# DDR4_SDRAM.net
KiCad netlist of a schematic drawn in Altium Designer
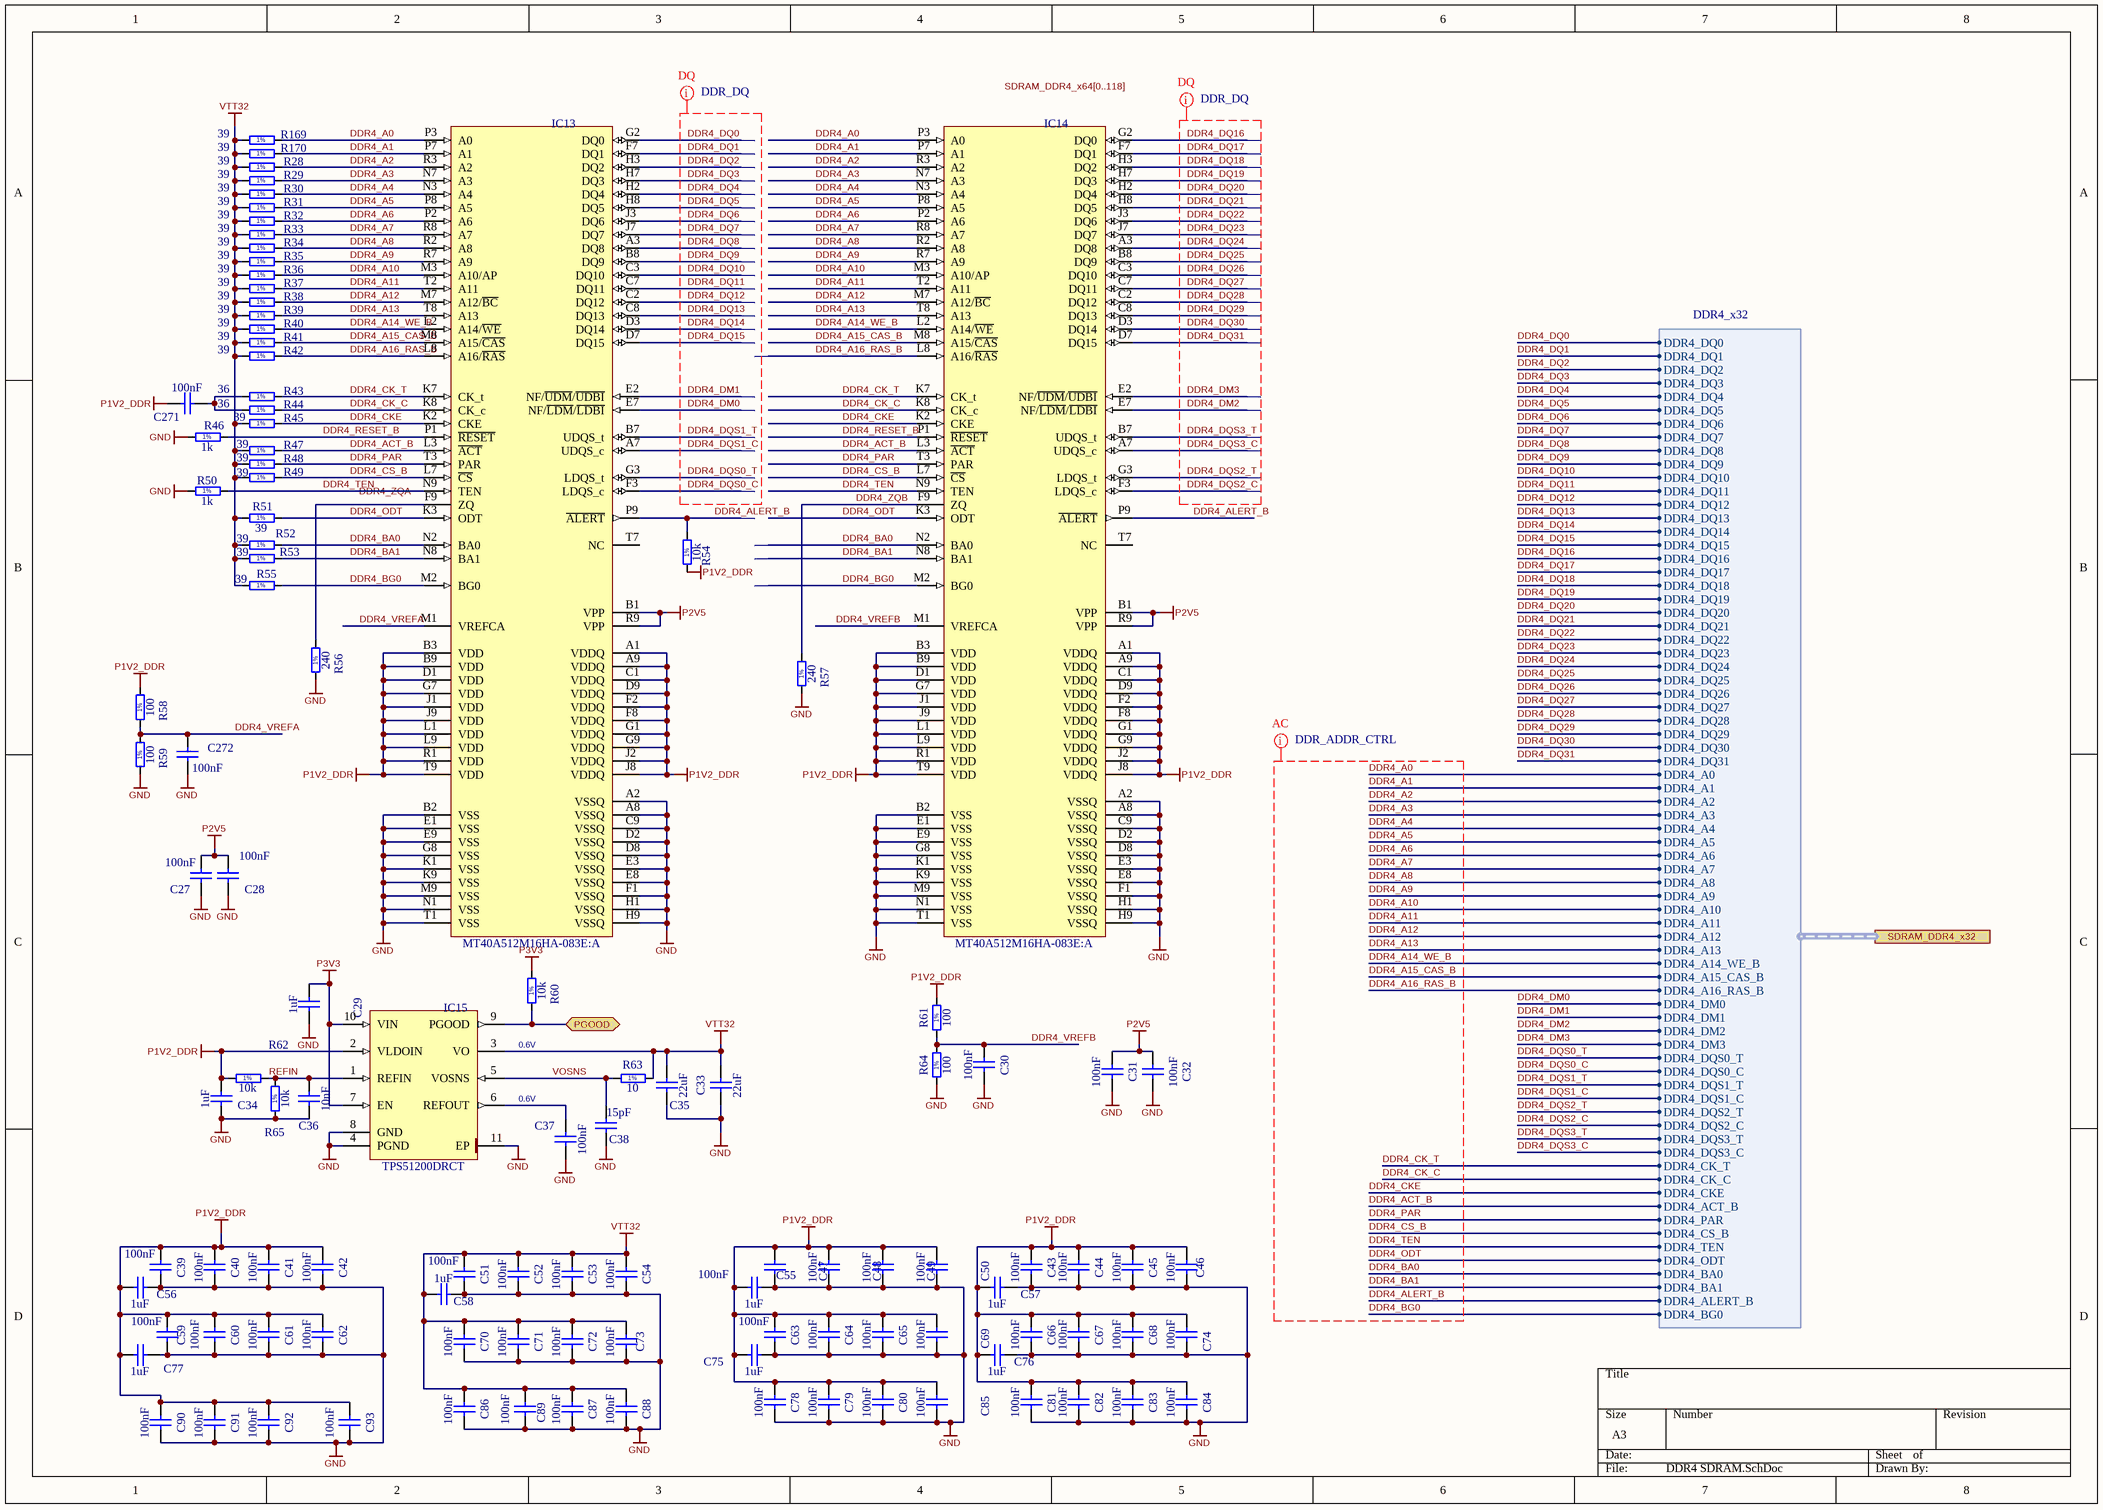
[diagram p0: DDR4 SDRAM.SchDoc]

(export (version "E")
  (design (tool "Eeschema 10.0.6"))
  (components
    (comp (ref "C27")
      (value "100nF")
      (footprint "CAPC0603X33N")
      (description "Non-polarised capacitor")
      (fields
        (field (name "MANUFACTURER PART NUMBER") "CC0201_100NF_6.3V_10%_X5R")
        (field (name "MANUFACTURER") "GENERIC")
        (field (name "AUTHOR") "CERN DEM JLC")
      )
      (libsource (lib "Capacitors") (part "Capacitor - non polarized"))
    )
    (comp (ref "C28")
      (value "100nF")
      (footprint "CAPC0603X33N")
      (description "Non-polarised capacitor")
      (fields
        (field (name "MANUFACTURER PART NUMBER") "CC0201_100NF_6.3V_10%_X5R")
        (field (name "MANUFACTURER") "GENERIC")
        (field (name "AUTHOR") "CERN DEM JLC")
      )
      (libsource (lib "Capacitors") (part "Capacitor - non polarized"))
    )
    (comp (ref "C29")
      (value "1uF")
      (footprint "CAPC1005X55N")
      (description "Non-polarised capacitor")
      (fields
        (field (name "MANUFACTURER PART NUMBER") "CC0402_1UF_16V_10%_X5R")
        (field (name "MANUFACTURER") "GENERIC")
        (field (name "AUTHOR") "CERN DEM JLC")
      )
      (libsource (lib "Capacitors") (part "Capacitor - non polarized"))
    )
    (comp (ref "C30")
      (value "100nF")
      (footprint "CAPC0603X33N")
      (description "Non-polarised capacitor")
      (fields
        (field (name "MANUFACTURER PART NUMBER") "CC0201_100NF_6.3V_10%_X5R")
        (field (name "MANUFACTURER") "GENERIC")
        (field (name "AUTHOR") "CERN DEM JLC")
      )
      (libsource (lib "Capacitors") (part "Capacitor - non polarized"))
    )
    (comp (ref "C31")
      (value "100nF")
      (footprint "CAPC0603X33N")
      (description "Non-polarised capacitor")
      (fields
        (field (name "MANUFACTURER PART NUMBER") "CC0201_100NF_6.3V_10%_X5R")
        (field (name "MANUFACTURER") "GENERIC")
        (field (name "AUTHOR") "CERN DEM JLC")
      )
      (libsource (lib "Capacitors") (part "Capacitor - non polarized"))
    )
    (comp (ref "C32")
      (value "100nF")
      (footprint "CAPC0603X33N")
      (description "Non-polarised capacitor")
      (fields
        (field (name "MANUFACTURER PART NUMBER") "CC0201_100NF_6.3V_10%_X5R")
        (field (name "MANUFACTURER") "GENERIC")
        (field (name "AUTHOR") "CERN DEM JLC")
      )
      (libsource (lib "Capacitors") (part "Capacitor - non polarized"))
    )
    (comp (ref "C33")
      (value "22uF")
      (footprint "CAPC2012X135N")
      (description "Non-polarised capacitor")
      (fields
        (field (name "MANUFACTURER PART NUMBER") "CC0805_22UF_10V_+80%-20%_Y5V")
        (field (name "MANUFACTURER") "GENERIC")
        (field (name "AUTHOR") "CERN DEM JLC")
      )
      (libsource (lib "Capacitors") (part "Capacitor - non polarized"))
    )
    (comp (ref "C34")
      (value "1uF")
      (footprint "CAPC1005X55N")
      (description "Non-polarised capacitor")
      (fields
        (field (name "MANUFACTURER PART NUMBER") "CC0402_1UF_16V_10%_X5R")
        (field (name "MANUFACTURER") "GENERIC")
        (field (name "AUTHOR") "CERN DEM JLC")
      )
      (libsource (lib "Capacitors") (part "Capacitor - non polarized"))
    )
    (comp (ref "C35")
      (value "22uF")
      (footprint "CAPC2012X135N")
      (description "Non-polarised capacitor")
      (fields
        (field (name "MANUFACTURER PART NUMBER") "CC0805_22UF_10V_+80%-20%_Y5V")
        (field (name "MANUFACTURER") "GENERIC")
        (field (name "AUTHOR") "CERN DEM JLC")
      )
      (libsource (lib "Capacitors") (part "Capacitor - non polarized"))
    )
    (comp (ref "C36")
      (value "10nF")
      (footprint "CAPC1005X55N")
      (description "Non-polarised capacitor")
      (fields
        (field (name "MANUFACTURER PART NUMBER") "CC0402_10NF_25V_10%_X7R")
        (field (name "MANUFACTURER") "GENERIC")
        (field (name "AUTHOR") "CERN DEM JLC")
      )
      (libsource (lib "Capacitors") (part "Capacitor - non polarized"))
    )
    (comp (ref "C37")
      (value "100nF")
      (footprint "CAPC0603X33N")
      (description "Non-polarised capacitor")
      (fields
        (field (name "MANUFACTURER PART NUMBER") "CC0201_100NF_6.3V_10%_X5R")
        (field (name "MANUFACTURER") "GENERIC")
        (field (name "AUTHOR") "CERN DEM JLC")
      )
      (libsource (lib "Capacitors") (part "Capacitor - non polarized"))
    )
    (comp (ref "C38")
      (value "15pF")
      (footprint "CAPC1005X55N")
      (description "Non-polarised capacitor")
      (fields
        (field (name "MANUFACTURER PART NUMBER") "CC0402_15PF_50V_5%_C0G")
        (field (name "MANUFACTURER") "GENERIC")
        (field (name "AUTHOR") "CERN DEM JLC")
      )
      (libsource (lib "Capacitors") (part "Capacitor - non polarized"))
    )
    (comp (ref "C39")
      (value "100nF")
      (footprint "CAPC0603X33N")
      (description "Non-polarised capacitor")
      (fields
        (field (name "MANUFACTURER PART NUMBER") "CC0201_100NF_6.3V_10%_X5R")
        (field (name "MANUFACTURER") "GENERIC")
        (field (name "AUTHOR") "CERN DEM JLC")
      )
      (libsource (lib "Capacitors") (part "Capacitor - non polarized"))
    )
    (comp (ref "C40")
      (value "100nF")
      (footprint "CAPC0603X33N")
      (description "Non-polarised capacitor")
      (fields
        (field (name "MANUFACTURER PART NUMBER") "CC0201_100NF_6.3V_10%_X5R")
        (field (name "MANUFACTURER") "GENERIC")
        (field (name "AUTHOR") "CERN DEM JLC")
      )
      (libsource (lib "Capacitors") (part "Capacitor - non polarized"))
    )
    (comp (ref "C41")
      (value "100nF")
      (footprint "CAPC0603X33N")
      (description "Non-polarised capacitor")
      (fields
        (field (name "MANUFACTURER PART NUMBER") "CC0201_100NF_6.3V_10%_X5R")
        (field (name "MANUFACTURER") "GENERIC")
        (field (name "AUTHOR") "CERN DEM JLC")
      )
      (libsource (lib "Capacitors") (part "Capacitor - non polarized"))
    )
    (comp (ref "C42")
      (value "100nF")
      (footprint "CAPC0603X33N")
      (description "Non-polarised capacitor")
      (fields
        (field (name "MANUFACTURER PART NUMBER") "CC0201_100NF_6.3V_10%_X5R")
        (field (name "MANUFACTURER") "GENERIC")
        (field (name "AUTHOR") "CERN DEM JLC")
      )
      (libsource (lib "Capacitors") (part "Capacitor - non polarized"))
    )
    (comp (ref "C43")
      (value "100nF")
      (footprint "CAPC0603X33N")
      (description "Non-polarised capacitor")
      (fields
        (field (name "MANUFACTURER PART NUMBER") "CC0201_100NF_6.3V_10%_X5R")
        (field (name "MANUFACTURER") "GENERIC")
        (field (name "AUTHOR") "CERN DEM JLC")
      )
      (libsource (lib "Capacitors") (part "Capacitor - non polarized"))
    )
    (comp (ref "C44")
      (value "100nF")
      (footprint "CAPC0603X33N")
      (description "Non-polarised capacitor")
      (fields
        (field (name "MANUFACTURER PART NUMBER") "CC0201_100NF_6.3V_10%_X5R")
        (field (name "MANUFACTURER") "GENERIC")
        (field (name "AUTHOR") "CERN DEM JLC")
      )
      (libsource (lib "Capacitors") (part "Capacitor - non polarized"))
    )
    (comp (ref "C45")
      (value "100nF")
      (footprint "CAPC0603X33N")
      (description "Non-polarised capacitor")
      (fields
        (field (name "MANUFACTURER PART NUMBER") "CC0201_100NF_6.3V_10%_X5R")
        (field (name "MANUFACTURER") "GENERIC")
        (field (name "AUTHOR") "CERN DEM JLC")
      )
      (libsource (lib "Capacitors") (part "Capacitor - non polarized"))
    )
    (comp (ref "C46")
      (value "100nF")
      (footprint "CAPC0603X33N")
      (description "Non-polarised capacitor")
      (fields
        (field (name "MANUFACTURER PART NUMBER") "CC0201_100NF_6.3V_10%_X5R")
        (field (name "MANUFACTURER") "GENERIC")
        (field (name "AUTHOR") "CERN DEM JLC")
      )
      (libsource (lib "Capacitors") (part "Capacitor - non polarized"))
    )
    (comp (ref "C47")
      (value "100nF")
      (footprint "CAPC0603X33N")
      (description "Non-polarised capacitor")
      (fields
        (field (name "MANUFACTURER PART NUMBER") "CC0201_100NF_6.3V_10%_X5R")
        (field (name "MANUFACTURER") "GENERIC")
        (field (name "AUTHOR") "CERN DEM JLC")
      )
      (libsource (lib "Capacitors") (part "Capacitor - non polarized"))
    )
    (comp (ref "C48")
      (value "100nF")
      (footprint "CAPC0603X33N")
      (description "Non-polarised capacitor")
      (fields
        (field (name "MANUFACTURER PART NUMBER") "CC0201_100NF_6.3V_10%_X5R")
        (field (name "MANUFACTURER") "GENERIC")
        (field (name "AUTHOR") "CERN DEM JLC")
      )
      (libsource (lib "Capacitors") (part "Capacitor - non polarized"))
    )
    (comp (ref "C49")
      (value "100nF")
      (footprint "CAPC0603X33N")
      (description "Non-polarised capacitor")
      (fields
        (field (name "MANUFACTURER PART NUMBER") "CC0201_100NF_6.3V_10%_X5R")
        (field (name "MANUFACTURER") "GENERIC")
        (field (name "AUTHOR") "CERN DEM JLC")
      )
      (libsource (lib "Capacitors") (part "Capacitor - non polarized"))
    )
    (comp (ref "C50")
      (value "100nF")
      (footprint "CAPC0603X33N")
      (description "Non-polarised capacitor")
      (fields
        (field (name "MANUFACTURER PART NUMBER") "CC0201_100NF_6.3V_10%_X5R")
        (field (name "MANUFACTURER") "GENERIC")
        (field (name "AUTHOR") "CERN DEM JLC")
      )
      (libsource (lib "Capacitors") (part "Capacitor - non polarized"))
    )
    (comp (ref "C51")
      (value "100nF")
      (footprint "CAPC0603X33N")
      (description "Non-polarised capacitor")
      (fields
        (field (name "MANUFACTURER PART NUMBER") "CC0201_100NF_6.3V_10%_X5R")
        (field (name "MANUFACTURER") "GENERIC")
        (field (name "AUTHOR") "CERN DEM JLC")
      )
      (libsource (lib "Capacitors") (part "Capacitor - non polarized"))
    )
    (comp (ref "C52")
      (value "100nF")
      (footprint "CAPC0603X33N")
      (description "Non-polarised capacitor")
      (fields
        (field (name "MANUFACTURER PART NUMBER") "CC0201_100NF_6.3V_10%_X5R")
        (field (name "MANUFACTURER") "GENERIC")
        (field (name "AUTHOR") "CERN DEM JLC")
      )
      (libsource (lib "Capacitors") (part "Capacitor - non polarized"))
    )
    (comp (ref "C53")
      (value "100nF")
      (footprint "CAPC0603X33N")
      (description "Non-polarised capacitor")
      (fields
        (field (name "MANUFACTURER PART NUMBER") "CC0201_100NF_6.3V_10%_X5R")
        (field (name "MANUFACTURER") "GENERIC")
        (field (name "AUTHOR") "CERN DEM JLC")
      )
      (libsource (lib "Capacitors") (part "Capacitor - non polarized"))
    )
    (comp (ref "C54")
      (value "100nF")
      (footprint "CAPC0603X33N")
      (description "Non-polarised capacitor")
      (fields
        (field (name "MANUFACTURER PART NUMBER") "CC0201_100NF_6.3V_10%_X5R")
        (field (name "MANUFACTURER") "GENERIC")
        (field (name "AUTHOR") "CERN DEM JLC")
      )
      (libsource (lib "Capacitors") (part "Capacitor - non polarized"))
    )
    (comp (ref "C55")
      (value "1uF")
      (footprint "CAPC1005X55N")
      (description "Non-polarised capacitor")
      (fields
        (field (name "MANUFACTURER PART NUMBER") "CC0402_1UF_16V_10%_X5R")
        (field (name "MANUFACTURER") "GENERIC")
        (field (name "AUTHOR") "CERN DEM JLC")
      )
      (libsource (lib "Capacitors") (part "Capacitor - non polarized"))
    )
    (comp (ref "C56")
      (value "1uF")
      (footprint "CAPC1005X55N")
      (description "Non-polarised capacitor")
      (fields
        (field (name "MANUFACTURER PART NUMBER") "CC0402_1UF_16V_10%_X5R")
        (field (name "MANUFACTURER") "GENERIC")
        (field (name "AUTHOR") "CERN DEM JLC")
      )
      (libsource (lib "Capacitors") (part "Capacitor - non polarized"))
    )
    (comp (ref "C57")
      (value "1uF")
      (footprint "CAPC1005X55N")
      (description "Non-polarised capacitor")
      (fields
        (field (name "MANUFACTURER PART NUMBER") "CC0402_1UF_16V_10%_X5R")
        (field (name "MANUFACTURER") "GENERIC")
        (field (name "AUTHOR") "CERN DEM JLC")
      )
      (libsource (lib "Capacitors") (part "Capacitor - non polarized"))
    )
    (comp (ref "C58")
      (value "1uF")
      (footprint "CAPC1005X55N")
      (description "Non-polarised capacitor")
      (fields
        (field (name "MANUFACTURER PART NUMBER") "CC0402_1UF_16V_10%_X5R")
        (field (name "MANUFACTURER") "GENERIC")
        (field (name "AUTHOR") "CERN DEM JLC")
      )
      (libsource (lib "Capacitors") (part "Capacitor - non polarized"))
    )
    (comp (ref "C59")
      (value "100nF")
      (footprint "CAPC0603X33N")
      (description "Non-polarised capacitor")
      (fields
        (field (name "MANUFACTURER PART NUMBER") "CC0201_100NF_6.3V_10%_X5R")
        (field (name "MANUFACTURER") "GENERIC")
        (field (name "AUTHOR") "CERN DEM JLC")
      )
      (libsource (lib "Capacitors") (part "Capacitor - non polarized"))
    )
    (comp (ref "C60")
      (value "100nF")
      (footprint "CAPC0603X33N")
      (description "Non-polarised capacitor")
      (fields
        (field (name "MANUFACTURER PART NUMBER") "CC0201_100NF_6.3V_10%_X5R")
        (field (name "MANUFACTURER") "GENERIC")
        (field (name "AUTHOR") "CERN DEM JLC")
      )
      (libsource (lib "Capacitors") (part "Capacitor - non polarized"))
    )
    (comp (ref "C61")
      (value "100nF")
      (footprint "CAPC0603X33N")
      (description "Non-polarised capacitor")
      (fields
        (field (name "MANUFACTURER PART NUMBER") "CC0201_100NF_6.3V_10%_X5R")
        (field (name "MANUFACTURER") "GENERIC")
        (field (name "AUTHOR") "CERN DEM JLC")
      )
      (libsource (lib "Capacitors") (part "Capacitor - non polarized"))
    )
    (comp (ref "C62")
      (value "100nF")
      (footprint "CAPC0603X33N")
      (description "Non-polarised capacitor")
      (fields
        (field (name "MANUFACTURER PART NUMBER") "CC0201_100NF_6.3V_10%_X5R")
        (field (name "MANUFACTURER") "GENERIC")
        (field (name "AUTHOR") "CERN DEM JLC")
      )
      (libsource (lib "Capacitors") (part "Capacitor - non polarized"))
    )
    (comp (ref "C63")
      (value "100nF")
      (footprint "CAPC0603X33N")
      (description "Non-polarised capacitor")
      (fields
        (field (name "MANUFACTURER PART NUMBER") "CC0201_100NF_6.3V_10%_X5R")
        (field (name "MANUFACTURER") "GENERIC")
        (field (name "AUTHOR") "CERN DEM JLC")
      )
      (libsource (lib "Capacitors") (part "Capacitor - non polarized"))
    )
    (comp (ref "C64")
      (value "100nF")
      (footprint "CAPC0603X33N")
      (description "Non-polarised capacitor")
      (fields
        (field (name "MANUFACTURER PART NUMBER") "CC0201_100NF_6.3V_10%_X5R")
        (field (name "MANUFACTURER") "GENERIC")
        (field (name "AUTHOR") "CERN DEM JLC")
      )
      (libsource (lib "Capacitors") (part "Capacitor - non polarized"))
    )
    (comp (ref "C65")
      (value "100nF")
      (footprint "CAPC0603X33N")
      (description "Non-polarised capacitor")
      (fields
        (field (name "MANUFACTURER PART NUMBER") "CC0201_100NF_6.3V_10%_X5R")
        (field (name "MANUFACTURER") "GENERIC")
        (field (name "AUTHOR") "CERN DEM JLC")
      )
      (libsource (lib "Capacitors") (part "Capacitor - non polarized"))
    )
    (comp (ref "C66")
      (value "100nF")
      (footprint "CAPC0603X33N")
      (description "Non-polarised capacitor")
      (fields
        (field (name "MANUFACTURER PART NUMBER") "CC0201_100NF_6.3V_10%_X5R")
        (field (name "MANUFACTURER") "GENERIC")
        (field (name "AUTHOR") "CERN DEM JLC")
      )
      (libsource (lib "Capacitors") (part "Capacitor - non polarized"))
    )
    (comp (ref "C67")
      (value "100nF")
      (footprint "CAPC0603X33N")
      (description "Non-polarised capacitor")
      (fields
        (field (name "MANUFACTURER PART NUMBER") "CC0201_100NF_6.3V_10%_X5R")
        (field (name "MANUFACTURER") "GENERIC")
        (field (name "AUTHOR") "CERN DEM JLC")
      )
      (libsource (lib "Capacitors") (part "Capacitor - non polarized"))
    )
    (comp (ref "C68")
      (value "100nF")
      (footprint "CAPC0603X33N")
      (description "Non-polarised capacitor")
      (fields
        (field (name "MANUFACTURER PART NUMBER") "CC0201_100NF_6.3V_10%_X5R")
        (field (name "MANUFACTURER") "GENERIC")
        (field (name "AUTHOR") "CERN DEM JLC")
      )
      (libsource (lib "Capacitors") (part "Capacitor - non polarized"))
    )
    (comp (ref "C69")
      (value "100nF")
      (footprint "CAPC0603X33N")
      (description "Non-polarised capacitor")
      (fields
        (field (name "MANUFACTURER PART NUMBER") "CC0201_100NF_6.3V_10%_X5R")
        (field (name "MANUFACTURER") "GENERIC")
        (field (name "AUTHOR") "CERN DEM JLC")
      )
      (libsource (lib "Capacitors") (part "Capacitor - non polarized"))
    )
    (comp (ref "C70")
      (value "100nF")
      (footprint "CAPC0603X33N")
      (description "Non-polarised capacitor")
      (fields
        (field (name "MANUFACTURER PART NUMBER") "CC0201_100NF_6.3V_10%_X5R")
        (field (name "MANUFACTURER") "GENERIC")
        (field (name "AUTHOR") "CERN DEM JLC")
      )
      (libsource (lib "Capacitors") (part "Capacitor - non polarized"))
    )
    (comp (ref "C71")
      (value "100nF")
      (footprint "CAPC0603X33N")
      (description "Non-polarised capacitor")
      (fields
        (field (name "MANUFACTURER PART NUMBER") "CC0201_100NF_6.3V_10%_X5R")
        (field (name "MANUFACTURER") "GENERIC")
        (field (name "AUTHOR") "CERN DEM JLC")
      )
      (libsource (lib "Capacitors") (part "Capacitor - non polarized"))
    )
    (comp (ref "C72")
      (value "100nF")
      (footprint "CAPC0603X33N")
      (description "Non-polarised capacitor")
      (fields
        (field (name "MANUFACTURER PART NUMBER") "CC0201_100NF_6.3V_10%_X5R")
        (field (name "MANUFACTURER") "GENERIC")
        (field (name "AUTHOR") "CERN DEM JLC")
      )
      (libsource (lib "Capacitors") (part "Capacitor - non polarized"))
    )
    (comp (ref "C73")
      (value "100nF")
      (footprint "CAPC0603X33N")
      (description "Non-polarised capacitor")
      (fields
        (field (name "MANUFACTURER PART NUMBER") "CC0201_100NF_6.3V_10%_X5R")
        (field (name "MANUFACTURER") "GENERIC")
        (field (name "AUTHOR") "CERN DEM JLC")
      )
      (libsource (lib "Capacitors") (part "Capacitor - non polarized"))
    )
    (comp (ref "C74")
      (value "100nF")
      (footprint "CAPC0603X33N")
      (description "Non-polarised capacitor")
      (fields
        (field (name "MANUFACTURER PART NUMBER") "CC0201_100NF_6.3V_10%_X5R")
        (field (name "MANUFACTURER") "GENERIC")
        (field (name "AUTHOR") "CERN DEM JLC")
      )
      (libsource (lib "Capacitors") (part "Capacitor - non polarized"))
    )
    (comp (ref "C75")
      (value "1uF")
      (footprint "CAPC1005X55N")
      (description "Non-polarised capacitor")
      (fields
        (field (name "MANUFACTURER PART NUMBER") "CC0402_1UF_16V_10%_X5R")
        (field (name "MANUFACTURER") "GENERIC")
        (field (name "AUTHOR") "CERN DEM JLC")
      )
      (libsource (lib "Capacitors") (part "Capacitor - non polarized"))
    )
    (comp (ref "C76")
      (value "1uF")
      (footprint "CAPC1005X55N")
      (description "Non-polarised capacitor")
      (fields
        (field (name "MANUFACTURER PART NUMBER") "CC0402_1UF_16V_10%_X5R")
        (field (name "MANUFACTURER") "GENERIC")
        (field (name "AUTHOR") "CERN DEM JLC")
      )
      (libsource (lib "Capacitors") (part "Capacitor - non polarized"))
    )
    (comp (ref "C77")
      (value "1uF")
      (footprint "CAPC1005X55N")
      (description "Non-polarised capacitor")
      (fields
        (field (name "MANUFACTURER PART NUMBER") "CC0402_1UF_16V_10%_X5R")
        (field (name "MANUFACTURER") "GENERIC")
        (field (name "AUTHOR") "CERN DEM JLC")
      )
      (libsource (lib "Capacitors") (part "Capacitor - non polarized"))
    )
    (comp (ref "C78")
      (value "100nF")
      (footprint "CAPC0603X33N")
      (description "Non-polarised capacitor")
      (fields
        (field (name "MANUFACTURER PART NUMBER") "CC0201_100NF_6.3V_10%_X5R")
        (field (name "MANUFACTURER") "GENERIC")
        (field (name "AUTHOR") "CERN DEM JLC")
      )
      (libsource (lib "Capacitors") (part "Capacitor - non polarized"))
    )
    (comp (ref "C79")
      (value "100nF")
      (footprint "CAPC0603X33N")
      (description "Non-polarised capacitor")
      (fields
        (field (name "MANUFACTURER PART NUMBER") "CC0201_100NF_6.3V_10%_X5R")
        (field (name "MANUFACTURER") "GENERIC")
        (field (name "AUTHOR") "CERN DEM JLC")
      )
      (libsource (lib "Capacitors") (part "Capacitor - non polarized"))
    )
    (comp (ref "C80")
      (value "100nF")
      (footprint "CAPC0603X33N")
      (description "Non-polarised capacitor")
      (fields
        (field (name "MANUFACTURER PART NUMBER") "CC0201_100NF_6.3V_10%_X5R")
        (field (name "MANUFACTURER") "GENERIC")
        (field (name "AUTHOR") "CERN DEM JLC")
      )
      (libsource (lib "Capacitors") (part "Capacitor - non polarized"))
    )
    (comp (ref "C81")
      (value "100nF")
      (footprint "CAPC0603X33N")
      (description "Non-polarised capacitor")
      (fields
        (field (name "MANUFACTURER PART NUMBER") "CC0201_100NF_6.3V_10%_X5R")
        (field (name "MANUFACTURER") "GENERIC")
        (field (name "AUTHOR") "CERN DEM JLC")
      )
      (libsource (lib "Capacitors") (part "Capacitor - non polarized"))
    )
    (comp (ref "C82")
      (value "100nF")
      (footprint "CAPC0603X33N")
      (description "Non-polarised capacitor")
      (fields
        (field (name "MANUFACTURER PART NUMBER") "CC0201_100NF_6.3V_10%_X5R")
        (field (name "MANUFACTURER") "GENERIC")
        (field (name "AUTHOR") "CERN DEM JLC")
      )
      (libsource (lib "Capacitors") (part "Capacitor - non polarized"))
    )
    (comp (ref "C83")
      (value "100nF")
      (footprint "CAPC0603X33N")
      (description "Non-polarised capacitor")
      (fields
        (field (name "MANUFACTURER PART NUMBER") "CC0201_100NF_6.3V_10%_X5R")
        (field (name "MANUFACTURER") "GENERIC")
        (field (name "AUTHOR") "CERN DEM JLC")
      )
      (libsource (lib "Capacitors") (part "Capacitor - non polarized"))
    )
    (comp (ref "C84")
      (value "100nF")
      (footprint "CAPC0603X33N")
      (description "Non-polarised capacitor")
      (fields
        (field (name "MANUFACTURER PART NUMBER") "CC0201_100NF_6.3V_10%_X5R")
        (field (name "MANUFACTURER") "GENERIC")
        (field (name "AUTHOR") "CERN DEM JLC")
      )
      (libsource (lib "Capacitors") (part "Capacitor - non polarized"))
    )
    (comp (ref "C85")
      (value "100nF")
      (footprint "CAPC0603X33N")
      (description "Non-polarised capacitor")
      (fields
        (field (name "MANUFACTURER PART NUMBER") "CC0201_100NF_6.3V_10%_X5R")
        (field (name "MANUFACTURER") "GENERIC")
        (field (name "AUTHOR") "CERN DEM JLC")
      )
      (libsource (lib "Capacitors") (part "Capacitor - non polarized"))
    )
    (comp (ref "C86")
      (value "100nF")
      (footprint "CAPC0603X33N")
      (description "Non-polarised capacitor")
      (fields
        (field (name "MANUFACTURER PART NUMBER") "CC0201_100NF_6.3V_10%_X5R")
        (field (name "MANUFACTURER") "GENERIC")
        (field (name "AUTHOR") "CERN DEM JLC")
      )
      (libsource (lib "Capacitors") (part "Capacitor - non polarized"))
    )
    (comp (ref "C87")
      (value "100nF")
      (footprint "CAPC0603X33N")
      (description "Non-polarised capacitor")
      (fields
        (field (name "MANUFACTURER PART NUMBER") "CC0201_100NF_6.3V_10%_X5R")
        (field (name "MANUFACTURER") "GENERIC")
        (field (name "AUTHOR") "CERN DEM JLC")
      )
      (libsource (lib "Capacitors") (part "Capacitor - non polarized"))
    )
    (comp (ref "C88")
      (value "100nF")
      (footprint "CAPC0603X33N")
      (description "Non-polarised capacitor")
      (fields
        (field (name "MANUFACTURER PART NUMBER") "CC0201_100NF_6.3V_10%_X5R")
        (field (name "MANUFACTURER") "GENERIC")
        (field (name "AUTHOR") "CERN DEM JLC")
      )
      (libsource (lib "Capacitors") (part "Capacitor - non polarized"))
    )
    (comp (ref "C89")
      (value "100nF")
      (footprint "CAPC0603X33N")
      (description "Non-polarised capacitor")
      (fields
        (field (name "MANUFACTURER PART NUMBER") "CC0201_100NF_6.3V_10%_X5R")
        (field (name "MANUFACTURER") "GENERIC")
        (field (name "AUTHOR") "CERN DEM JLC")
      )
      (libsource (lib "Capacitors") (part "Capacitor - non polarized"))
    )
    (comp (ref "C90")
      (value "100nF")
      (footprint "CAPC0603X33N")
      (description "Non-polarised capacitor")
      (fields
        (field (name "MANUFACTURER PART NUMBER") "CC0201_100NF_6.3V_10%_X5R")
        (field (name "MANUFACTURER") "GENERIC")
        (field (name "AUTHOR") "CERN DEM JLC")
      )
      (libsource (lib "Capacitors") (part "Capacitor - non polarized"))
    )
    (comp (ref "C91")
      (value "100nF")
      (footprint "CAPC0603X33N")
      (description "Non-polarised capacitor")
      (fields
        (field (name "MANUFACTURER PART NUMBER") "CC0201_100NF_6.3V_10%_X5R")
        (field (name "MANUFACTURER") "GENERIC")
        (field (name "AUTHOR") "CERN DEM JLC")
      )
      (libsource (lib "Capacitors") (part "Capacitor - non polarized"))
    )
    (comp (ref "C92")
      (value "100nF")
      (footprint "CAPC0603X33N")
      (description "Non-polarised capacitor")
      (fields
        (field (name "MANUFACTURER PART NUMBER") "CC0201_100NF_6.3V_10%_X5R")
        (field (name "MANUFACTURER") "GENERIC")
        (field (name "AUTHOR") "CERN DEM JLC")
      )
      (libsource (lib "Capacitors") (part "Capacitor - non polarized"))
    )
    (comp (ref "C93")
      (value "100nF")
      (footprint "CAPC0603X33N")
      (description "Non-polarised capacitor")
      (fields
        (field (name "MANUFACTURER PART NUMBER") "CC0201_100NF_6.3V_10%_X5R")
        (field (name "MANUFACTURER") "GENERIC")
        (field (name "AUTHOR") "CERN DEM JLC")
      )
      (libsource (lib "Capacitors") (part "Capacitor - non polarized"))
    )
    (comp (ref "C271")
      (value "100nF")
      (footprint "CAPC0603X33N")
      (description "Non-polarised capacitor")
      (fields
        (field (name "MANUFACTURER PART NUMBER") "CC0201_100NF_6.3V_10%_X5R")
        (field (name "MANUFACTURER") "GENERIC")
        (field (name "AUTHOR") "CERN DEM JLC")
      )
      (libsource (lib "Capacitors") (part "Capacitor - non polarized"))
    )
    (comp (ref "C272")
      (value "100nF")
      (footprint "CAPC0603X33N")
      (description "Non-polarised capacitor")
      (fields
        (field (name "MANUFACTURER PART NUMBER") "CC0201_100NF_6.3V_10%_X5R")
        (field (name "MANUFACTURER") "GENERIC")
        (field (name "AUTHOR") "CERN DEM JLC")
      )
      (libsource (lib "Capacitors") (part "Capacitor - non polarized"))
    )
    (comp (ref "IC13")
      (value "MT40A512M16HA-083E:A")
      (footprint "BGA96C80P9X16_900X1400X120")
      (description "+1.2V, 8Gb (512 Meg x 16 x 8 Banks) DDR4 SDRAM")
      (fields (field (name "MANUFACTURER") "MICRON TECHNOLOGY") (field (name "AUTHOR") "CERN DEM MR"))
      (libsource (lib "ICs And Semiconductors") (part "MT40A512M16HA"))
    )
    (comp (ref "IC14")
      (value "MT40A512M16HA-083E:A")
      (footprint "BGA96C80P9X16_900X1400X120")
      (description "+1.2V, 8Gb (512 Meg x 16 x 8 Banks) DDR4 SDRAM")
      (fields (field (name "MANUFACTURER") "MICRON TECHNOLOGY") (field (name "AUTHOR") "CERN DEM MR"))
      (libsource (lib "ICs And Semiconductors") (part "MT40A512M16HA"))
    )
    (comp (ref "IC15")
      (value "TPS51200DRCT")
      (footprint "TEXAS_DRC (S-PVSON-N10)")
      (description "Sink/Source DDR Termination Regulator")
      (fields (field (name "MANUFACTURER") "TEXAS INSTRUMENTS") (field (name "AUTHOR") "CERN DEM JLC"))
      (libsource (lib "ICs And Semiconductors") (part "TPS51200DRC"))
    )
    (comp (ref "R28")
      (value "39")
      (footprint "RESC1005X40N")
      (description "Resistor - 1%")
      (fields
        (field (name "MANUFACTURER PART NUMBER") "R0402_39R_1%_0.0625W_100PPM")
        (field (name "MANUFACTURER") "GENERIC")
        (field (name "AUTHOR") "CERN DEM JLC")
      )
      (libsource (lib "Resistors") (part "Resistor - 1%"))
    )
    (comp (ref "R29")
      (value "39")
      (footprint "RESC1005X40N")
      (description "Resistor - 1%")
      (fields
        (field (name "MANUFACTURER PART NUMBER") "R0402_39R_1%_0.0625W_100PPM")
        (field (name "MANUFACTURER") "GENERIC")
        (field (name "AUTHOR") "CERN DEM JLC")
      )
      (libsource (lib "Resistors") (part "Resistor - 1%"))
    )
    (comp (ref "R30")
      (value "39")
      (footprint "RESC1005X40N")
      (description "Resistor - 1%")
      (fields
        (field (name "MANUFACTURER PART NUMBER") "R0402_39R_1%_0.0625W_100PPM")
        (field (name "MANUFACTURER") "GENERIC")
        (field (name "AUTHOR") "CERN DEM JLC")
      )
      (libsource (lib "Resistors") (part "Resistor - 1%"))
    )
    (comp (ref "R31")
      (value "39")
      (footprint "RESC1005X40N")
      (description "Resistor - 1%")
      (fields
        (field (name "MANUFACTURER PART NUMBER") "R0402_39R_1%_0.0625W_100PPM")
        (field (name "MANUFACTURER") "GENERIC")
        (field (name "AUTHOR") "CERN DEM JLC")
      )
      (libsource (lib "Resistors") (part "Resistor - 1%"))
    )
    (comp (ref "R32")
      (value "39")
      (footprint "RESC1005X40N")
      (description "Resistor - 1%")
      (fields
        (field (name "MANUFACTURER PART NUMBER") "R0402_39R_1%_0.0625W_100PPM")
        (field (name "MANUFACTURER") "GENERIC")
        (field (name "AUTHOR") "CERN DEM JLC")
      )
      (libsource (lib "Resistors") (part "Resistor - 1%"))
    )
    (comp (ref "R33")
      (value "39")
      (footprint "RESC1005X40N")
      (description "Resistor - 1%")
      (fields
        (field (name "MANUFACTURER PART NUMBER") "R0402_39R_1%_0.0625W_100PPM")
        (field (name "MANUFACTURER") "GENERIC")
        (field (name "AUTHOR") "CERN DEM JLC")
      )
      (libsource (lib "Resistors") (part "Resistor - 1%"))
    )
    (comp (ref "R34")
      (value "39")
      (footprint "RESC1005X40N")
      (description "Resistor - 1%")
      (fields
        (field (name "MANUFACTURER PART NUMBER") "R0402_39R_1%_0.0625W_100PPM")
        (field (name "MANUFACTURER") "GENERIC")
        (field (name "AUTHOR") "CERN DEM JLC")
      )
      (libsource (lib "Resistors") (part "Resistor - 1%"))
    )
    (comp (ref "R35")
      (value "39")
      (footprint "RESC1005X40N")
      (description "Resistor - 1%")
      (fields
        (field (name "MANUFACTURER PART NUMBER") "R0402_39R_1%_0.0625W_100PPM")
        (field (name "MANUFACTURER") "GENERIC")
        (field (name "AUTHOR") "CERN DEM JLC")
      )
      (libsource (lib "Resistors") (part "Resistor - 1%"))
    )
    (comp (ref "R36")
      (value "39")
      (footprint "RESC1005X40N")
      (description "Resistor - 1%")
      (fields
        (field (name "MANUFACTURER PART NUMBER") "R0402_39R_1%_0.0625W_100PPM")
        (field (name "MANUFACTURER") "GENERIC")
        (field (name "AUTHOR") "CERN DEM JLC")
      )
      (libsource (lib "Resistors") (part "Resistor - 1%"))
    )
    (comp (ref "R37")
      (value "39")
      (footprint "RESC1005X40N")
      (description "Resistor - 1%")
      (fields
        (field (name "MANUFACTURER PART NUMBER") "R0402_39R_1%_0.0625W_100PPM")
        (field (name "MANUFACTURER") "GENERIC")
        (field (name "AUTHOR") "CERN DEM JLC")
      )
      (libsource (lib "Resistors") (part "Resistor - 1%"))
    )
    (comp (ref "R38")
      (value "39")
      (footprint "RESC1005X40N")
      (description "Resistor - 1%")
      (fields
        (field (name "MANUFACTURER PART NUMBER") "R0402_39R_1%_0.0625W_100PPM")
        (field (name "MANUFACTURER") "GENERIC")
        (field (name "AUTHOR") "CERN DEM JLC")
      )
      (libsource (lib "Resistors") (part "Resistor - 1%"))
    )
    (comp (ref "R39")
      (value "39")
      (footprint "RESC1005X40N")
      (description "Resistor - 1%")
      (fields
        (field (name "MANUFACTURER PART NUMBER") "R0402_39R_1%_0.0625W_100PPM")
        (field (name "MANUFACTURER") "GENERIC")
        (field (name "AUTHOR") "CERN DEM JLC")
      )
      (libsource (lib "Resistors") (part "Resistor - 1%"))
    )
    (comp (ref "R40")
      (value "39")
      (footprint "RESC1005X40N")
      (description "Resistor - 1%")
      (fields
        (field (name "MANUFACTURER PART NUMBER") "R0402_39R_1%_0.0625W_100PPM")
        (field (name "MANUFACTURER") "GENERIC")
        (field (name "AUTHOR") "CERN DEM JLC")
      )
      (libsource (lib "Resistors") (part "Resistor - 1%"))
    )
    (comp (ref "R41")
      (value "39")
      (footprint "RESC1005X40N")
      (description "Resistor - 1%")
      (fields
        (field (name "MANUFACTURER PART NUMBER") "R0402_39R_1%_0.0625W_100PPM")
        (field (name "MANUFACTURER") "GENERIC")
        (field (name "AUTHOR") "CERN DEM JLC")
      )
      (libsource (lib "Resistors") (part "Resistor - 1%"))
    )
    (comp (ref "R42")
      (value "39")
      (footprint "RESC1005X40N")
      (description "Resistor - 1%")
      (fields
        (field (name "MANUFACTURER PART NUMBER") "R0402_39R_1%_0.0625W_100PPM")
        (field (name "MANUFACTURER") "GENERIC")
        (field (name "AUTHOR") "CERN DEM JLC")
      )
      (libsource (lib "Resistors") (part "Resistor - 1%"))
    )
    (comp (ref "R43")
      (value "36")
      (footprint "RESC1005X40N")
      (description "Resistor - 1%")
      (fields
        (field (name "MANUFACTURER PART NUMBER") "R0402_36R_1%_0.0625W_100PPM")
        (field (name "MANUFACTURER") "GENERIC")
        (field (name "AUTHOR") "CERN DEM JLC")
      )
      (libsource (lib "Resistors") (part "Resistor - 1%"))
    )
    (comp (ref "R44")
      (value "36")
      (footprint "RESC1005X40N")
      (description "Resistor - 1%")
      (fields
        (field (name "MANUFACTURER PART NUMBER") "R0402_36R_1%_0.0625W_100PPM")
        (field (name "MANUFACTURER") "GENERIC")
        (field (name "AUTHOR") "CERN DEM JLC")
      )
      (libsource (lib "Resistors") (part "Resistor - 1%"))
    )
    (comp (ref "R45")
      (value "39")
      (footprint "RESC1005X40N")
      (description "Resistor - 1%")
      (fields
        (field (name "MANUFACTURER PART NUMBER") "R0402_39R_1%_0.0625W_100PPM")
        (field (name "MANUFACTURER") "GENERIC")
        (field (name "AUTHOR") "CERN DEM JLC")
      )
      (libsource (lib "Resistors") (part "Resistor - 1%"))
    )
    (comp (ref "R46")
      (value "1k")
      (footprint "RESC1005X40N")
      (description "Resistor - 1%")
      (fields
        (field (name "MANUFACTURER PART NUMBER") "R0402_1K_1%_0.0625W_100PPM")
        (field (name "MANUFACTURER") "GENERIC")
        (field (name "AUTHOR") "CERN DEM JLC")
      )
      (libsource (lib "Resistors") (part "Resistor - 1%"))
    )
    (comp (ref "R47")
      (value "39")
      (footprint "RESC1005X40N")
      (description "Resistor - 1%")
      (fields
        (field (name "MANUFACTURER PART NUMBER") "R0402_39R_1%_0.0625W_100PPM")
        (field (name "MANUFACTURER") "GENERIC")
        (field (name "AUTHOR") "CERN DEM JLC")
      )
      (libsource (lib "Resistors") (part "Resistor - 1%"))
    )
    (comp (ref "R48")
      (value "39")
      (footprint "RESC1005X40N")
      (description "Resistor - 1%")
      (fields
        (field (name "MANUFACTURER PART NUMBER") "R0402_39R_1%_0.0625W_100PPM")
        (field (name "MANUFACTURER") "GENERIC")
        (field (name "AUTHOR") "CERN DEM JLC")
      )
      (libsource (lib "Resistors") (part "Resistor - 1%"))
    )
    (comp (ref "R49")
      (value "39")
      (footprint "RESC1005X40N")
      (description "Resistor - 1%")
      (fields
        (field (name "MANUFACTURER PART NUMBER") "R0402_39R_1%_0.0625W_100PPM")
        (field (name "MANUFACTURER") "GENERIC")
        (field (name "AUTHOR") "CERN DEM JLC")
      )
      (libsource (lib "Resistors") (part "Resistor - 1%"))
    )
    (comp (ref "R50")
      (value "1k")
      (footprint "RESC1005X40N")
      (description "Resistor - 1%")
      (fields
        (field (name "MANUFACTURER PART NUMBER") "R0402_1K_1%_0.0625W_100PPM")
        (field (name "MANUFACTURER") "GENERIC")
        (field (name "AUTHOR") "CERN DEM JLC")
      )
      (libsource (lib "Resistors") (part "Resistor - 1%"))
    )
    (comp (ref "R51")
      (value "39")
      (footprint "RESC1005X40N")
      (description "Resistor - 1%")
      (fields
        (field (name "MANUFACTURER PART NUMBER") "R0402_39R_1%_0.0625W_100PPM")
        (field (name "MANUFACTURER") "GENERIC")
        (field (name "AUTHOR") "CERN DEM JLC")
      )
      (libsource (lib "Resistors") (part "Resistor - 1%"))
    )
    (comp (ref "R52")
      (value "39")
      (footprint "RESC1005X40N")
      (description "Resistor - 1%")
      (fields
        (field (name "MANUFACTURER PART NUMBER") "R0402_39R_1%_0.0625W_100PPM")
        (field (name "MANUFACTURER") "GENERIC")
        (field (name "AUTHOR") "CERN DEM JLC")
      )
      (libsource (lib "Resistors") (part "Resistor - 1%"))
    )
    (comp (ref "R53")
      (value "39")
      (footprint "RESC1005X40N")
      (description "Resistor - 1%")
      (fields
        (field (name "MANUFACTURER PART NUMBER") "R0402_39R_1%_0.0625W_100PPM")
        (field (name "MANUFACTURER") "GENERIC")
        (field (name "AUTHOR") "CERN DEM JLC")
      )
      (libsource (lib "Resistors") (part "Resistor - 1%"))
    )
    (comp (ref "R54")
      (value "10k")
      (footprint "RESC1005X40N")
      (description "Resistor - 1%")
      (fields
        (field (name "MANUFACTURER PART NUMBER") "R0402_10K_1%_0.0625W_100PPM")
        (field (name "MANUFACTURER") "GENERIC")
        (field (name "AUTHOR") "CERN DEM JLC")
      )
      (libsource (lib "Resistors") (part "Resistor - 1%"))
    )
    (comp (ref "R55")
      (value "39")
      (footprint "RESC1005X40N")
      (description "Resistor - 1%")
      (fields
        (field (name "MANUFACTURER PART NUMBER") "R0402_39R_1%_0.0625W_100PPM")
        (field (name "MANUFACTURER") "GENERIC")
        (field (name "AUTHOR") "CERN DEM JLC")
      )
      (libsource (lib "Resistors") (part "Resistor - 1%"))
    )
    (comp (ref "R56")
      (value "240")
      (footprint "RESC1005X40N")
      (description "Resistor - 1%")
      (fields
        (field (name "MANUFACTURER PART NUMBER") "R0402_240R_1%_0.0625W_100PPM")
        (field (name "MANUFACTURER") "GENERIC")
        (field (name "AUTHOR") "CERN DEM JLC")
      )
      (libsource (lib "Resistors") (part "Resistor - 1%"))
    )
    (comp (ref "R57")
      (value "240")
      (footprint "RESC1005X40N")
      (description "Resistor - 1%")
      (fields
        (field (name "MANUFACTURER PART NUMBER") "R0402_240R_1%_0.0625W_100PPM")
        (field (name "MANUFACTURER") "GENERIC")
        (field (name "AUTHOR") "CERN DEM JLC")
      )
      (libsource (lib "Resistors") (part "Resistor - 1%"))
    )
    (comp (ref "R58")
      (value "100")
      (footprint "RESC1005X40N")
      (description "Resistor - 1%")
      (fields
        (field (name "MANUFACTURER PART NUMBER") "R0402_100R_1%_0.0625W_100PPM")
        (field (name "MANUFACTURER") "GENERIC")
        (field (name "AUTHOR") "CERN DEM JLC")
      )
      (libsource (lib "Resistors") (part "Resistor - 1%"))
    )
    (comp (ref "R59")
      (value "100")
      (footprint "RESC1005X40N")
      (description "Resistor - 1%")
      (fields
        (field (name "MANUFACTURER PART NUMBER") "R0402_100R_1%_0.0625W_100PPM")
        (field (name "MANUFACTURER") "GENERIC")
        (field (name "AUTHOR") "CERN DEM JLC")
      )
      (libsource (lib "Resistors") (part "Resistor - 1%"))
    )
    (comp (ref "R60")
      (value "10k")
      (footprint "RESC1005X40N")
      (description "Resistor - 1%")
      (fields
        (field (name "MANUFACTURER PART NUMBER") "R0402_10K_1%_0.0625W_100PPM")
        (field (name "MANUFACTURER") "GENERIC")
        (field (name "AUTHOR") "CERN DEM JLC")
      )
      (libsource (lib "Resistors") (part "Resistor - 1%"))
    )
    (comp (ref "R61")
      (value "100")
      (footprint "RESC1005X40N")
      (description "Resistor - 1%")
      (fields
        (field (name "MANUFACTURER PART NUMBER") "R0402_100R_1%_0.0625W_100PPM")
        (field (name "MANUFACTURER") "GENERIC")
        (field (name "AUTHOR") "CERN DEM JLC")
      )
      (libsource (lib "Resistors") (part "Resistor - 1%"))
    )
    (comp (ref "R62")
      (value "10k")
      (footprint "RESC1005X40N")
      (description "Resistor - 1%")
      (fields
        (field (name "MANUFACTURER PART NUMBER") "R0402_10K_1%_0.0625W_100PPM")
        (field (name "MANUFACTURER") "GENERIC")
        (field (name "AUTHOR") "CERN DEM JLC")
      )
      (libsource (lib "Resistors") (part "Resistor - 1%"))
    )
    (comp (ref "R63")
      (value "10")
      (footprint "RESC1005X40N")
      (description "Resistor - 1%")
      (fields
        (field (name "MANUFACTURER PART NUMBER") "R0402_10R_1%_0.0625W_200PPM")
        (field (name "MANUFACTURER") "GENERIC")
        (field (name "AUTHOR") "CERN DEM JLC")
      )
      (libsource (lib "Resistors") (part "Resistor - 1%"))
    )
    (comp (ref "R64")
      (value "100")
      (footprint "RESC1005X40N")
      (description "Resistor - 1%")
      (fields
        (field (name "MANUFACTURER PART NUMBER") "R0402_100R_1%_0.0625W_100PPM")
        (field (name "MANUFACTURER") "GENERIC")
        (field (name "AUTHOR") "CERN DEM JLC")
      )
      (libsource (lib "Resistors") (part "Resistor - 1%"))
    )
    (comp (ref "R65")
      (value "10k")
      (footprint "RESC1005X40N")
      (description "Resistor - 1%")
      (fields
        (field (name "MANUFACTURER PART NUMBER") "R0402_10K_1%_0.0625W_100PPM")
        (field (name "MANUFACTURER") "GENERIC")
        (field (name "AUTHOR") "CERN DEM JLC")
      )
      (libsource (lib "Resistors") (part "Resistor - 1%"))
    )
    (comp (ref "R169")
      (value "39")
      (footprint "RESC1005X40N")
      (description "Resistor - 1%")
      (fields
        (field (name "MANUFACTURER PART NUMBER") "R0402_39R_1%_0.0625W_100PPM")
        (field (name "MANUFACTURER") "GENERIC")
        (field (name "AUTHOR") "CERN DEM JLC")
      )
      (libsource (lib "Resistors") (part "Resistor - 1%"))
    )
    (comp (ref "R170")
      (value "39")
      (footprint "RESC1005X40N")
      (description "Resistor - 1%")
      (fields
        (field (name "MANUFACTURER PART NUMBER") "R0402_39R_1%_0.0625W_100PPM")
        (field (name "MANUFACTURER") "GENERIC")
        (field (name "AUTHOR") "CERN DEM JLC")
      )
      (libsource (lib "Resistors") (part "Resistor - 1%"))
    )
  )
  (nets
    (net (code "121") (name "/DDR4_A0") (class "Default")
      (node (ref "IC13") (pin "P3") (pinfunction "A0_P3") (pintype "input"))
      (node (ref "IC14") (pin "P3") (pinfunction "A0_P3") (pintype "input"))
      (node (ref "R169") (pin "2") (pinfunction "2_2") (pintype "passive"))
    )
    (net (code "122") (name "/DDR4_A1") (class "Default")
      (node (ref "IC13") (pin "P7") (pinfunction "A1_P7") (pintype "input"))
      (node (ref "IC14") (pin "P7") (pinfunction "A1_P7") (pintype "input"))
      (node (ref "R170") (pin "2") (pinfunction "2_2") (pintype "passive"))
    )
    (net (code "123") (name "/DDR4_A2") (class "Default")
      (node (ref "IC13") (pin "R3") (pinfunction "A2_R3") (pintype "input"))
      (node (ref "IC14") (pin "R3") (pinfunction "A2_R3") (pintype "input"))
      (node (ref "R28") (pin "2") (pinfunction "2_2") (pintype "passive"))
    )
    (net (code "124") (name "/DDR4_A3") (class "Default")
      (node (ref "IC13") (pin "N7") (pinfunction "A3_N7") (pintype "input"))
      (node (ref "IC14") (pin "N7") (pinfunction "A3_N7") (pintype "input"))
      (node (ref "R29") (pin "2") (pinfunction "2_2") (pintype "passive"))
    )
    (net (code "125") (name "/DDR4_A4") (class "Default")
      (node (ref "IC13") (pin "N3") (pinfunction "A4_N3") (pintype "input"))
      (node (ref "IC14") (pin "N3") (pinfunction "A4_N3") (pintype "input"))
      (node (ref "R30") (pin "2") (pinfunction "2_2") (pintype "passive"))
    )
    (net (code "126") (name "/DDR4_A5") (class "Default")
      (node (ref "IC13") (pin "P8") (pinfunction "A5_P8") (pintype "input"))
      (node (ref "IC14") (pin "P8") (pinfunction "A5_P8") (pintype "input"))
      (node (ref "R31") (pin "2") (pinfunction "2_2") (pintype "passive"))
    )
    (net (code "127") (name "/DDR4_A6") (class "Default")
      (node (ref "IC13") (pin "P2") (pinfunction "A6_P2") (pintype "input"))
      (node (ref "IC14") (pin "P2") (pinfunction "A6_P2") (pintype "input"))
      (node (ref "R32") (pin "2") (pinfunction "2_2") (pintype "passive"))
    )
    (net (code "128") (name "/DDR4_A7") (class "Default")
      (node (ref "IC13") (pin "R8") (pinfunction "A7_R8") (pintype "input"))
      (node (ref "IC14") (pin "R8") (pinfunction "A7_R8") (pintype "input"))
      (node (ref "R33") (pin "2") (pinfunction "2_2") (pintype "passive"))
    )
    (net (code "129") (name "/DDR4_A8") (class "Default")
      (node (ref "IC13") (pin "R2") (pinfunction "A8_R2") (pintype "input"))
      (node (ref "IC14") (pin "R2") (pinfunction "A8_R2") (pintype "input"))
      (node (ref "R34") (pin "2") (pinfunction "2_2") (pintype "passive"))
    )
    (net (code "130") (name "/DDR4_A9") (class "Default")
      (node (ref "IC13") (pin "R7") (pinfunction "A9_R7") (pintype "input"))
      (node (ref "IC14") (pin "R7") (pinfunction "A9_R7") (pintype "input"))
      (node (ref "R35") (pin "2") (pinfunction "2_2") (pintype "passive"))
    )
    (net (code "131") (name "/DDR4_A10") (class "Default")
      (node (ref "IC13") (pin "M3") (pinfunction "A10/AP_M3") (pintype "input"))
      (node (ref "IC14") (pin "M3") (pinfunction "A10/AP_M3") (pintype "input"))
      (node (ref "R36") (pin "2") (pinfunction "2_2") (pintype "passive"))
    )
    (net (code "132") (name "/DDR4_A11") (class "Default")
      (node (ref "IC13") (pin "T2") (pinfunction "A11_T2") (pintype "input"))
      (node (ref "IC14") (pin "T2") (pinfunction "A11_T2") (pintype "input"))
      (node (ref "R37") (pin "2") (pinfunction "2_2") (pintype "passive"))
    )
    (net (code "133") (name "/DDR4_A12") (class "Default")
      (node (ref "IC13") (pin "M7") (pinfunction "A12/~{BC}_M7") (pintype "input"))
      (node (ref "IC14") (pin "M7") (pinfunction "A12/~{BC}_M7") (pintype "input"))
      (node (ref "R38") (pin "2") (pinfunction "2_2") (pintype "passive"))
    )
    (net (code "134") (name "/DDR4_A13") (class "Default")
      (node (ref "IC13") (pin "T8") (pinfunction "A13_T8") (pintype "input"))
      (node (ref "IC14") (pin "T8") (pinfunction "A13_T8") (pintype "input"))
      (node (ref "R39") (pin "2") (pinfunction "2_2") (pintype "passive"))
    )
    (net (code "135") (name "/DDR4_A14_WE_B") (class "Default")
      (node (ref "IC13") (pin "L2") (pinfunction "A14/~{WE}_L2") (pintype "input"))
      (node (ref "IC14") (pin "L2") (pinfunction "A14/~{WE}_L2") (pintype "input"))
      (node (ref "R40") (pin "2") (pinfunction "2_2") (pintype "passive"))
    )
    (net (code "136") (name "/DDR4_A15_CAS_B") (class "Default")
      (node (ref "IC13") (pin "M8") (pinfunction "A15/~{CAS}_M8") (pintype "input"))
      (node (ref "IC14") (pin "M8") (pinfunction "A15/~{CAS}_M8") (pintype "input"))
      (node (ref "R41") (pin "2") (pinfunction "2_2") (pintype "passive"))
    )
    (net (code "137") (name "/DDR4_A16_RAS_B") (class "Default")
      (node (ref "IC13") (pin "L8") (pinfunction "A16/~{RAS}_L8") (pintype "input"))
      (node (ref "IC14") (pin "L8") (pinfunction "A16/~{RAS}_L8") (pintype "input"))
      (node (ref "R42") (pin "2") (pinfunction "2_2") (pintype "passive"))
    )
    (net (code "138") (name "/DDR4_ACT_B") (class "Default")
      (node (ref "IC13") (pin "L3") (pinfunction "~{ACT}_L3") (pintype "input"))
      (node (ref "IC14") (pin "L3") (pinfunction "~{ACT}_L3") (pintype "input"))
      (node (ref "R47") (pin "2") (pinfunction "2_2") (pintype "passive"))
    )
    (net (code "139") (name "/DDR4_ALERT_B") (class "Default")
      (node (ref "IC13") (pin "P9") (pinfunction "~{ALERT}_P9") (pintype "output"))
      (node (ref "IC14") (pin "P9") (pinfunction "~{ALERT}_P9") (pintype "output"))
      (node (ref "R54") (pin "2") (pinfunction "2_2") (pintype "passive"))
    )
    (net (code "140") (name "/DDR4_BA0") (class "Default")
      (node (ref "IC13") (pin "N2") (pinfunction "BA0_N2") (pintype "input"))
      (node (ref "IC14") (pin "N2") (pinfunction "BA0_N2") (pintype "input"))
      (node (ref "R52") (pin "2") (pinfunction "2_2") (pintype "passive"))
    )
    (net (code "141") (name "/DDR4_BA1") (class "Default")
      (node (ref "IC13") (pin "N8") (pinfunction "BA1_N8") (pintype "input"))
      (node (ref "IC14") (pin "N8") (pinfunction "BA1_N8") (pintype "input"))
      (node (ref "R53") (pin "2") (pinfunction "2_2") (pintype "passive"))
    )
    (net (code "142") (name "/DDR4_BG0") (class "Default")
      (node (ref "IC13") (pin "M2") (pinfunction "BG0_M2") (pintype "input"))
      (node (ref "IC14") (pin "M2") (pinfunction "BG0_M2") (pintype "input"))
      (node (ref "R55") (pin "2") (pinfunction "2_2") (pintype "passive"))
    )
    (net (code "143") (name "/DDR4_CKE") (class "Default")
      (node (ref "IC13") (pin "K2") (pinfunction "CKE_K2") (pintype "input"))
      (node (ref "IC14") (pin "K2") (pinfunction "CKE_K2") (pintype "input"))
      (node (ref "R45") (pin "2") (pinfunction "2_2") (pintype "passive"))
    )
    (net (code "144") (name "/DDR4_CK_C") (class "Default")
      (node (ref "IC13") (pin "K8") (pinfunction "CK_c_K8") (pintype "input"))
      (node (ref "IC14") (pin "K8") (pinfunction "CK_c_K8") (pintype "input"))
      (node (ref "R44") (pin "2") (pinfunction "2_2") (pintype "passive"))
    )
    (net (code "145") (name "/DDR4_CK_T") (class "Default")
      (node (ref "IC13") (pin "K7") (pinfunction "CK_t_K7") (pintype "input"))
      (node (ref "IC14") (pin "K7") (pinfunction "CK_t_K7") (pintype "input"))
      (node (ref "R43") (pin "2") (pinfunction "2_2") (pintype "passive"))
    )
    (net (code "146") (name "/DDR4_CS_B") (class "Default")
      (node (ref "IC13") (pin "L7") (pinfunction "~{CS}_L7") (pintype "input"))
      (node (ref "IC14") (pin "L7") (pinfunction "~{CS}_L7") (pintype "input"))
      (node (ref "R49") (pin "2") (pinfunction "2_2") (pintype "passive"))
    )
    (net (code "147") (name "/DDR4_DM0") (class "Default")
      (node (ref "IC13") (pin "E7") (pinfunction "NF/~{LDM}/~{LDBI}_E7") (pintype "input"))
    )
    (net (code "148") (name "/DDR4_DM1") (class "Default")
      (node (ref "IC13") (pin "E2") (pinfunction "NF/~{UDM}/~{UDBI}_E2") (pintype "input"))
    )
    (net (code "149") (name "/DDR4_DM2") (class "Default")
      (node (ref "IC14") (pin "E7") (pinfunction "NF/~{LDM}/~{LDBI}_E7") (pintype "input"))
    )
    (net (code "150") (name "/DDR4_DM3") (class "Default")
      (node (ref "IC14") (pin "E2") (pinfunction "NF/~{UDM}/~{UDBI}_E2") (pintype "input"))
    )
    (net (code "151") (name "/DDR4_DQ0") (class "Default")
      (node (ref "IC13") (pin "G2") (pinfunction "DQ0_G2") (pintype "bidirectional"))
    )
    (net (code "152") (name "/DDR4_DQ1") (class "Default")
      (node (ref "IC13") (pin "F7") (pinfunction "DQ1_F7") (pintype "bidirectional"))
    )
    (net (code "153") (name "/DDR4_DQ2") (class "Default")
      (node (ref "IC13") (pin "H3") (pinfunction "DQ2_H3") (pintype "bidirectional"))
    )
    (net (code "154") (name "/DDR4_DQ3") (class "Default")
      (node (ref "IC13") (pin "H7") (pinfunction "DQ3_H7") (pintype "bidirectional"))
    )
    (net (code "155") (name "/DDR4_DQ4") (class "Default")
      (node (ref "IC13") (pin "H2") (pinfunction "DQ4_H2") (pintype "bidirectional"))
    )
    (net (code "156") (name "/DDR4_DQ5") (class "Default")
      (node (ref "IC13") (pin "H8") (pinfunction "DQ5_H8") (pintype "bidirectional"))
    )
    (net (code "157") (name "/DDR4_DQ6") (class "Default")
      (node (ref "IC13") (pin "J3") (pinfunction "DQ6_J3") (pintype "bidirectional"))
    )
    (net (code "158") (name "/DDR4_DQ7") (class "Default")
      (node (ref "IC13") (pin "J7") (pinfunction "DQ7_J7") (pintype "bidirectional"))
    )
    (net (code "159") (name "/DDR4_DQ8") (class "Default")
      (node (ref "IC13") (pin "A3") (pinfunction "DQ8_A3") (pintype "bidirectional"))
    )
    (net (code "160") (name "/DDR4_DQ9") (class "Default")
      (node (ref "IC13") (pin "B8") (pinfunction "DQ9_B8") (pintype "bidirectional"))
    )
    (net (code "161") (name "/DDR4_DQ10") (class "Default")
      (node (ref "IC13") (pin "C3") (pinfunction "DQ10_C3") (pintype "bidirectional"))
    )
    (net (code "162") (name "/DDR4_DQ11") (class "Default")
      (node (ref "IC13") (pin "C7") (pinfunction "DQ11_C7") (pintype "bidirectional"))
    )
    (net (code "163") (name "/DDR4_DQ12") (class "Default")
      (node (ref "IC13") (pin "C2") (pinfunction "DQ12_C2") (pintype "bidirectional"))
    )
    (net (code "164") (name "/DDR4_DQ13") (class "Default")
      (node (ref "IC13") (pin "C8") (pinfunction "DQ13_C8") (pintype "bidirectional"))
    )
    (net (code "165") (name "/DDR4_DQ14") (class "Default")
      (node (ref "IC13") (pin "D3") (pinfunction "DQ14_D3") (pintype "bidirectional"))
    )
    (net (code "166") (name "/DDR4_DQ15") (class "Default")
      (node (ref "IC13") (pin "D7") (pinfunction "DQ15_D7") (pintype "bidirectional"))
    )
    (net (code "167") (name "/DDR4_DQ16") (class "Default")
      (node (ref "IC14") (pin "G2") (pinfunction "DQ0_G2") (pintype "bidirectional"))
    )
    (net (code "168") (name "/DDR4_DQ17") (class "Default")
      (node (ref "IC14") (pin "F7") (pinfunction "DQ1_F7") (pintype "bidirectional"))
    )
    (net (code "169") (name "/DDR4_DQ18") (class "Default")
      (node (ref "IC14") (pin "H3") (pinfunction "DQ2_H3") (pintype "bidirectional"))
    )
    (net (code "170") (name "/DDR4_DQ19") (class "Default")
      (node (ref "IC14") (pin "H7") (pinfunction "DQ3_H7") (pintype "bidirectional"))
    )
    (net (code "171") (name "/DDR4_DQ20") (class "Default")
      (node (ref "IC14") (pin "H2") (pinfunction "DQ4_H2") (pintype "bidirectional"))
    )
    (net (code "172") (name "/DDR4_DQ21") (class "Default")
      (node (ref "IC14") (pin "H8") (pinfunction "DQ5_H8") (pintype "bidirectional"))
    )
    (net (code "173") (name "/DDR4_DQ22") (class "Default")
      (node (ref "IC14") (pin "J3") (pinfunction "DQ6_J3") (pintype "bidirectional"))
    )
    (net (code "174") (name "/DDR4_DQ23") (class "Default")
      (node (ref "IC14") (pin "J7") (pinfunction "DQ7_J7") (pintype "bidirectional"))
    )
    (net (code "175") (name "/DDR4_DQ24") (class "Default")
      (node (ref "IC14") (pin "A3") (pinfunction "DQ8_A3") (pintype "bidirectional"))
    )
    (net (code "176") (name "/DDR4_DQ25") (class "Default")
      (node (ref "IC14") (pin "B8") (pinfunction "DQ9_B8") (pintype "bidirectional"))
    )
    (net (code "177") (name "/DDR4_DQ26") (class "Default")
      (node (ref "IC14") (pin "C3") (pinfunction "DQ10_C3") (pintype "bidirectional"))
    )
    (net (code "178") (name "/DDR4_DQ27") (class "Default")
      (node (ref "IC14") (pin "C7") (pinfunction "DQ11_C7") (pintype "bidirectional"))
    )
    (net (code "179") (name "/DDR4_DQ28") (class "Default")
      (node (ref "IC14") (pin "C2") (pinfunction "DQ12_C2") (pintype "bidirectional"))
    )
    (net (code "180") (name "/DDR4_DQ29") (class "Default")
      (node (ref "IC14") (pin "C8") (pinfunction "DQ13_C8") (pintype "bidirectional"))
    )
    (net (code "181") (name "/DDR4_DQ30") (class "Default")
      (node (ref "IC14") (pin "D3") (pinfunction "DQ14_D3") (pintype "bidirectional"))
    )
    (net (code "182") (name "/DDR4_DQ31") (class "Default")
      (node (ref "IC14") (pin "D7") (pinfunction "DQ15_D7") (pintype "bidirectional"))
    )
    (net (code "183") (name "/DDR4_DQS0_C") (class "Default")
      (node (ref "IC13") (pin "F3") (pinfunction "LDQS_c_F3") (pintype "bidirectional"))
    )
    (net (code "184") (name "/DDR4_DQS0_T") (class "Default")
      (node (ref "IC13") (pin "G3") (pinfunction "LDQS_t_G3") (pintype "bidirectional"))
    )
    (net (code "185") (name "/DDR4_DQS1_C") (class "Default")
      (node (ref "IC13") (pin "A7") (pinfunction "UDQS_c_A7") (pintype "bidirectional"))
    )
    (net (code "186") (name "/DDR4_DQS1_T") (class "Default")
      (node (ref "IC13") (pin "B7") (pinfunction "UDQS_t_B7") (pintype "bidirectional"))
    )
    (net (code "187") (name "/DDR4_DQS2_C") (class "Default")
      (node (ref "IC14") (pin "F3") (pinfunction "LDQS_c_F3") (pintype "bidirectional"))
    )
    (net (code "188") (name "/DDR4_DQS2_T") (class "Default")
      (node (ref "IC14") (pin "G3") (pinfunction "LDQS_t_G3") (pintype "bidirectional"))
    )
    (net (code "189") (name "/DDR4_DQS3_C") (class "Default")
      (node (ref "IC14") (pin "A7") (pinfunction "UDQS_c_A7") (pintype "bidirectional"))
    )
    (net (code "190") (name "/DDR4_DQS3_T") (class "Default")
      (node (ref "IC14") (pin "B7") (pinfunction "UDQS_t_B7") (pintype "bidirectional"))
    )
    (net (code "191") (name "/DDR4_ODT") (class "Default")
      (node (ref "IC13") (pin "K3") (pinfunction "ODT_K3") (pintype "input"))
      (node (ref "IC14") (pin "K3") (pinfunction "ODT_K3") (pintype "input"))
      (node (ref "R51") (pin "2") (pinfunction "2_2") (pintype "passive"))
    )
    (net (code "192") (name "/DDR4_PAR") (class "Default")
      (node (ref "IC13") (pin "T3") (pinfunction "PAR_T3") (pintype "input"))
      (node (ref "IC14") (pin "T3") (pinfunction "PAR_T3") (pintype "input"))
      (node (ref "R48") (pin "2") (pinfunction "2_2") (pintype "passive"))
    )
    (net (code "193") (name "/DDR4_RESET_B") (class "Default")
      (node (ref "IC13") (pin "P1") (pinfunction "~{RESET}_P1") (pintype "input"))
      (node (ref "IC14") (pin "P1") (pinfunction "~{RESET}_P1") (pintype "input"))
      (node (ref "R46") (pin "2") (pinfunction "2_2") (pintype "passive"))
    )
    (net (code "194") (name "/DDR4_TEN") (class "Default")
      (node (ref "IC13") (pin "N9") (pinfunction "TEN_N9") (pintype "input"))
      (node (ref "IC14") (pin "N9") (pinfunction "TEN_N9") (pintype "input"))
      (node (ref "R50") (pin "2") (pinfunction "2_2") (pintype "passive"))
    )
    (net (code "195") (name "/DDR4_VREFA") (class "Default")
      (node (ref "C272") (pin "1") (pinfunction "1_1") (pintype "passive"))
      (node (ref "IC13") (pin "M1") (pinfunction "VREFCA_M1") (pintype "power_in"))
      (node (ref "R58") (pin "1") (pinfunction "1_1") (pintype "passive"))
      (node (ref "R59") (pin "2") (pinfunction "2_2") (pintype "passive"))
    )
    (net (code "196") (name "/DDR4_VREFB") (class "Default")
      (node (ref "C30") (pin "1") (pinfunction "1_1") (pintype "passive"))
      (node (ref "IC14") (pin "M1") (pinfunction "VREFCA_M1") (pintype "power_in"))
      (node (ref "R61") (pin "1") (pinfunction "1_1") (pintype "passive"))
      (node (ref "R64") (pin "2") (pinfunction "2_2") (pintype "passive"))
    )
    (net (code "198") (name "/DDR4_ZQB") (class "Default")
      (node (ref "IC14") (pin "F9") (pinfunction "ZQ_F9") (pintype "power_in"))
      (node (ref "R57") (pin "2") (pinfunction "2_2") (pintype "passive"))
    )
    (net (code "199") (name "/PGOOD") (class "Default")
      (node (ref "IC15") (pin "9") (pinfunction "PGOOD_9") (pintype "output"))
      (node (ref "R60") (pin "1") (pinfunction "1_1") (pintype "passive"))
    )
    (net (code "200") (name "/REFIN") (class "Default")
      (node (ref "C36") (pin "2") (pinfunction "2_2") (pintype "passive"))
      (node (ref "IC15") (pin "1") (pinfunction "REFIN_1") (pintype "input"))
      (node (ref "R62") (pin "2") (pinfunction "2_2") (pintype "passive"))
      (node (ref "R65") (pin "2") (pinfunction "2_2") (pintype "passive"))
    )
    (net (code "202") (name "/VOSNS") (class "Default")
      (node (ref "C38") (pin "2") (pinfunction "2_2") (pintype "passive"))
      (node (ref "IC15") (pin "5") (pinfunction "VOSNS_5") (pintype "input"))
      (node (ref "R63") (pin "1") (pinfunction "1_1") (pintype "passive"))
    )
    (net (code "204") (name "GND") (class "Default")
      (node (ref "C27") (pin "2") (pinfunction "2_2") (pintype "passive"))
      (node (ref "C272") (pin "2") (pinfunction "2_2") (pintype "passive"))
      (node (ref "C28") (pin "2") (pinfunction "2_2") (pintype "passive"))
      (node (ref "C29") (pin "2") (pinfunction "2_2") (pintype "passive"))
      (node (ref "C30") (pin "2") (pinfunction "2_2") (pintype "passive"))
      (node (ref "C31") (pin "2") (pinfunction "2_2") (pintype "passive"))
      (node (ref "C32") (pin "2") (pinfunction "2_2") (pintype "passive"))
      (node (ref "C33") (pin "1") (pinfunction "1_1") (pintype "passive"))
      (node (ref "C34") (pin "2") (pinfunction "2_2") (pintype "passive"))
      (node (ref "C35") (pin "1") (pinfunction "1_1") (pintype "passive"))
      (node (ref "C36") (pin "1") (pinfunction "1_1") (pintype "passive"))
      (node (ref "C37") (pin "1") (pinfunction "1_1") (pintype "passive"))
      (node (ref "C38") (pin "1") (pinfunction "1_1") (pintype "passive"))
      (node (ref "C39") (pin "2") (pinfunction "2_2") (pintype "passive"))
      (node (ref "C40") (pin "2") (pinfunction "2_2") (pintype "passive"))
      (node (ref "C41") (pin "2") (pinfunction "2_2") (pintype "passive"))
      (node (ref "C42") (pin "2") (pinfunction "2_2") (pintype "passive"))
      (node (ref "C43") (pin "2") (pinfunction "2_2") (pintype "passive"))
      (node (ref "C44") (pin "2") (pinfunction "2_2") (pintype "passive"))
      (node (ref "C45") (pin "2") (pinfunction "2_2") (pintype "passive"))
      (node (ref "C46") (pin "2") (pinfunction "2_2") (pintype "passive"))
      (node (ref "C47") (pin "2") (pinfunction "2_2") (pintype "passive"))
      (node (ref "C48") (pin "2") (pinfunction "2_2") (pintype "passive"))
      (node (ref "C49") (pin "2") (pinfunction "2_2") (pintype "passive"))
      (node (ref "C50") (pin "2") (pinfunction "2_2") (pintype "passive"))
      (node (ref "C51") (pin "2") (pinfunction "2_2") (pintype "passive"))
      (node (ref "C52") (pin "2") (pinfunction "2_2") (pintype "passive"))
      (node (ref "C53") (pin "2") (pinfunction "2_2") (pintype "passive"))
      (node (ref "C54") (pin "2") (pinfunction "2_2") (pintype "passive"))
      (node (ref "C55") (pin "2") (pinfunction "2_2") (pintype "passive"))
      (node (ref "C56") (pin "2") (pinfunction "2_2") (pintype "passive"))
      (node (ref "C57") (pin "2") (pinfunction "2_2") (pintype "passive"))
      (node (ref "C58") (pin "2") (pinfunction "2_2") (pintype "passive"))
      (node (ref "C59") (pin "2") (pinfunction "2_2") (pintype "passive"))
      (node (ref "C60") (pin "2") (pinfunction "2_2") (pintype "passive"))
      (node (ref "C61") (pin "2") (pinfunction "2_2") (pintype "passive"))
      (node (ref "C62") (pin "2") (pinfunction "2_2") (pintype "passive"))
      (node (ref "C63") (pin "2") (pinfunction "2_2") (pintype "passive"))
      (node (ref "C64") (pin "2") (pinfunction "2_2") (pintype "passive"))
      (node (ref "C65") (pin "2") (pinfunction "2_2") (pintype "passive"))
      (node (ref "C66") (pin "2") (pinfunction "2_2") (pintype "passive"))
      (node (ref "C67") (pin "2") (pinfunction "2_2") (pintype "passive"))
      (node (ref "C68") (pin "2") (pinfunction "2_2") (pintype "passive"))
      (node (ref "C69") (pin "2") (pinfunction "2_2") (pintype "passive"))
      (node (ref "C70") (pin "2") (pinfunction "2_2") (pintype "passive"))
      (node (ref "C71") (pin "2") (pinfunction "2_2") (pintype "passive"))
      (node (ref "C72") (pin "2") (pinfunction "2_2") (pintype "passive"))
      (node (ref "C73") (pin "2") (pinfunction "2_2") (pintype "passive"))
      (node (ref "C74") (pin "2") (pinfunction "2_2") (pintype "passive"))
      (node (ref "C75") (pin "2") (pinfunction "2_2") (pintype "passive"))
      (node (ref "C76") (pin "2") (pinfunction "2_2") (pintype "passive"))
      (node (ref "C77") (pin "2") (pinfunction "2_2") (pintype "passive"))
      (node (ref "C78") (pin "2") (pinfunction "2_2") (pintype "passive"))
      (node (ref "C79") (pin "2") (pinfunction "2_2") (pintype "passive"))
      (node (ref "C80") (pin "2") (pinfunction "2_2") (pintype "passive"))
      (node (ref "C81") (pin "2") (pinfunction "2_2") (pintype "passive"))
      (node (ref "C82") (pin "2") (pinfunction "2_2") (pintype "passive"))
      (node (ref "C83") (pin "2") (pinfunction "2_2") (pintype "passive"))
      (node (ref "C84") (pin "2") (pinfunction "2_2") (pintype "passive"))
      (node (ref "C85") (pin "2") (pinfunction "2_2") (pintype "passive"))
      (node (ref "C86") (pin "2") (pinfunction "2_2") (pintype "passive"))
      (node (ref "C87") (pin "2") (pinfunction "2_2") (pintype "passive"))
      (node (ref "C88") (pin "2") (pinfunction "2_2") (pintype "passive"))
      (node (ref "C89") (pin "2") (pinfunction "2_2") (pintype "passive"))
      (node (ref "C90") (pin "2") (pinfunction "2_2") (pintype "passive"))
      (node (ref "C91") (pin "2") (pinfunction "2_2") (pintype "passive"))
      (node (ref "C92") (pin "2") (pinfunction "2_2") (pintype "passive"))
      (node (ref "C93") (pin "1") (pinfunction "1_1") (pintype "passive"))
      (node (ref "IC13") (pin "A2") (pinfunction "VSSQ_A2") (pintype "power_in"))
      (node (ref "IC13") (pin "A8") (pinfunction "VSSQ_A8") (pintype "power_in"))
      (node (ref "IC13") (pin "B2") (pinfunction "VSS_B2") (pintype "power_in"))
      (node (ref "IC13") (pin "C9") (pinfunction "VSSQ_C9") (pintype "power_in"))
      (node (ref "IC13") (pin "D2") (pinfunction "VSSQ_D2") (pintype "power_in"))
      (node (ref "IC13") (pin "D8") (pinfunction "VSSQ_D8") (pintype "power_in"))
      (node (ref "IC13") (pin "E1") (pinfunction "VSS_E1") (pintype "power_in"))
      (node (ref "IC13") (pin "E3") (pinfunction "VSSQ_E3") (pintype "power_in"))
      (node (ref "IC13") (pin "E8") (pinfunction "VSSQ_E8") (pintype "power_in"))
      (node (ref "IC13") (pin "E9") (pinfunction "VSS_E9") (pintype "power_in"))
      (node (ref "IC13") (pin "F1") (pinfunction "VSSQ_F1") (pintype "power_in"))
      (node (ref "IC13") (pin "G8") (pinfunction "VSS_G8") (pintype "power_in"))
      (node (ref "IC13") (pin "H1") (pinfunction "VSSQ_H1") (pintype "power_in"))
      (node (ref "IC13") (pin "H9") (pinfunction "VSSQ_H9") (pintype "power_in"))
      (node (ref "IC13") (pin "K1") (pinfunction "VSS_K1") (pintype "power_in"))
      (node (ref "IC13") (pin "K9") (pinfunction "VSS_K9") (pintype "power_in"))
      (node (ref "IC13") (pin "M9") (pinfunction "VSS_M9") (pintype "power_in"))
      (node (ref "IC13") (pin "N1") (pinfunction "VSS_N1") (pintype "power_in"))
      (node (ref "IC13") (pin "T1") (pinfunction "VSS_T1") (pintype "power_in"))
      (node (ref "IC14") (pin "A2") (pinfunction "VSSQ_A2") (pintype "power_in"))
      (node (ref "IC14") (pin "A8") (pinfunction "VSSQ_A8") (pintype "power_in"))
      (node (ref "IC14") (pin "B2") (pinfunction "VSS_B2") (pintype "power_in"))
      (node (ref "IC14") (pin "C9") (pinfunction "VSSQ_C9") (pintype "power_in"))
      (node (ref "IC14") (pin "D2") (pinfunction "VSSQ_D2") (pintype "power_in"))
      (node (ref "IC14") (pin "D8") (pinfunction "VSSQ_D8") (pintype "power_in"))
      (node (ref "IC14") (pin "E1") (pinfunction "VSS_E1") (pintype "power_in"))
      (node (ref "IC14") (pin "E3") (pinfunction "VSSQ_E3") (pintype "power_in"))
      (node (ref "IC14") (pin "E8") (pinfunction "VSSQ_E8") (pintype "power_in"))
      (node (ref "IC14") (pin "E9") (pinfunction "VSS_E9") (pintype "power_in"))
      (node (ref "IC14") (pin "F1") (pinfunction "VSSQ_F1") (pintype "power_in"))
      (node (ref "IC14") (pin "G8") (pinfunction "VSS_G8") (pintype "power_in"))
      (node (ref "IC14") (pin "H1") (pinfunction "VSSQ_H1") (pintype "power_in"))
      (node (ref "IC14") (pin "H9") (pinfunction "VSSQ_H9") (pintype "power_in"))
      (node (ref "IC14") (pin "K1") (pinfunction "VSS_K1") (pintype "power_in"))
      (node (ref "IC14") (pin "K9") (pinfunction "VSS_K9") (pintype "power_in"))
      (node (ref "IC14") (pin "M9") (pinfunction "VSS_M9") (pintype "power_in"))
      (node (ref "IC14") (pin "N1") (pinfunction "VSS_N1") (pintype "power_in"))
      (node (ref "IC14") (pin "T1") (pinfunction "VSS_T1") (pintype "power_in"))
      (node (ref "IC15") (pin "11") (pinfunction "EP_11") (pintype "power_in"))
      (node (ref "IC15") (pin "4") (pinfunction "PGND_4") (pintype "power_in"))
      (node (ref "IC15") (pin "8") (pinfunction "GND_8") (pintype "power_in"))
      (node (ref "R46") (pin "1") (pinfunction "1_1") (pintype "passive"))
      (node (ref "R50") (pin "1") (pinfunction "1_1") (pintype "passive"))
      (node (ref "R56") (pin "1") (pinfunction "1_1") (pintype "passive"))
      (node (ref "R57") (pin "1") (pinfunction "1_1") (pintype "passive"))
      (node (ref "R59") (pin "1") (pinfunction "1_1") (pintype "passive"))
      (node (ref "R64") (pin "1") (pinfunction "1_1") (pintype "passive"))
      (node (ref "R65") (pin "1") (pinfunction "1_1") (pintype "passive"))
    )
    (net (code "205") (name "Net-(C271-Pad1)") (class "Default")
      (node (ref "C271") (pin "1") (pinfunction "1_1") (pintype "passive"))
      (node (ref "R43") (pin "1") (pinfunction "1_1") (pintype "passive"))
      (node (ref "R44") (pin "1") (pinfunction "1_1") (pintype "passive"))
    )
    (net (code "206") (name "Net-(IC13-ZQ)") (class "Default")
      (node (ref "IC13") (pin "F9") (pinfunction "ZQ_F9") (pintype "power_in"))
      (node (ref "R56") (pin "2") (pinfunction "2_2") (pintype "passive"))
    )
    (net (code "207") (name "Net-(IC15-REFOUT)") (class "Default")
      (node (ref "C37") (pin "2") (pinfunction "2_2") (pintype "passive"))
      (node (ref "IC15") (pin "6") (pinfunction "REFOUT_6") (pintype "output"))
    )
    (net (code "208") (name "P1V2_DDR") (class "Default")
      (node (ref "C271") (pin "2") (pinfunction "2_2") (pintype "passive"))
      (node (ref "C34") (pin "1") (pinfunction "1_1") (pintype "passive"))
      (node (ref "C39") (pin "1") (pinfunction "1_1") (pintype "passive"))
      (node (ref "C40") (pin "1") (pinfunction "1_1") (pintype "passive"))
      (node (ref "C41") (pin "1") (pinfunction "1_1") (pintype "passive"))
      (node (ref "C42") (pin "1") (pinfunction "1_1") (pintype "passive"))
      (node (ref "C43") (pin "1") (pinfunction "1_1") (pintype "passive"))
      (node (ref "C44") (pin "1") (pinfunction "1_1") (pintype "passive"))
      (node (ref "C45") (pin "1") (pinfunction "1_1") (pintype "passive"))
      (node (ref "C46") (pin "1") (pinfunction "1_1") (pintype "passive"))
      (node (ref "C47") (pin "1") (pinfunction "1_1") (pintype "passive"))
      (node (ref "C48") (pin "1") (pinfunction "1_1") (pintype "passive"))
      (node (ref "C49") (pin "1") (pinfunction "1_1") (pintype "passive"))
      (node (ref "C50") (pin "1") (pinfunction "1_1") (pintype "passive"))
      (node (ref "C55") (pin "1") (pinfunction "1_1") (pintype "passive"))
      (node (ref "C56") (pin "1") (pinfunction "1_1") (pintype "passive"))
      (node (ref "C57") (pin "1") (pinfunction "1_1") (pintype "passive"))
      (node (ref "C59") (pin "1") (pinfunction "1_1") (pintype "passive"))
      (node (ref "C60") (pin "1") (pinfunction "1_1") (pintype "passive"))
      (node (ref "C61") (pin "1") (pinfunction "1_1") (pintype "passive"))
      (node (ref "C62") (pin "1") (pinfunction "1_1") (pintype "passive"))
      (node (ref "C63") (pin "1") (pinfunction "1_1") (pintype "passive"))
      (node (ref "C64") (pin "1") (pinfunction "1_1") (pintype "passive"))
      (node (ref "C65") (pin "1") (pinfunction "1_1") (pintype "passive"))
      (node (ref "C66") (pin "1") (pinfunction "1_1") (pintype "passive"))
      (node (ref "C67") (pin "1") (pinfunction "1_1") (pintype "passive"))
      (node (ref "C68") (pin "1") (pinfunction "1_1") (pintype "passive"))
      (node (ref "C69") (pin "1") (pinfunction "1_1") (pintype "passive"))
      (node (ref "C74") (pin "1") (pinfunction "1_1") (pintype "passive"))
      (node (ref "C75") (pin "1") (pinfunction "1_1") (pintype "passive"))
      (node (ref "C76") (pin "1") (pinfunction "1_1") (pintype "passive"))
      (node (ref "C77") (pin "1") (pinfunction "1_1") (pintype "passive"))
      (node (ref "C78") (pin "1") (pinfunction "1_1") (pintype "passive"))
      (node (ref "C79") (pin "1") (pinfunction "1_1") (pintype "passive"))
      (node (ref "C80") (pin "1") (pinfunction "1_1") (pintype "passive"))
      (node (ref "C81") (pin "1") (pinfunction "1_1") (pintype "passive"))
      (node (ref "C82") (pin "1") (pinfunction "1_1") (pintype "passive"))
      (node (ref "C83") (pin "1") (pinfunction "1_1") (pintype "passive"))
      (node (ref "C84") (pin "1") (pinfunction "1_1") (pintype "passive"))
      (node (ref "C85") (pin "1") (pinfunction "1_1") (pintype "passive"))
      (node (ref "C90") (pin "1") (pinfunction "1_1") (pintype "passive"))
      (node (ref "C91") (pin "1") (pinfunction "1_1") (pintype "passive"))
      (node (ref "C92") (pin "1") (pinfunction "1_1") (pintype "passive"))
      (node (ref "C93") (pin "2") (pinfunction "2_2") (pintype "passive"))
      (node (ref "IC13") (pin "A1") (pinfunction "VDDQ_A1") (pintype "power_in"))
      (node (ref "IC13") (pin "A9") (pinfunction "VDDQ_A9") (pintype "power_in"))
      (node (ref "IC13") (pin "B3") (pinfunction "VDD_B3") (pintype "power_in"))
      (node (ref "IC13") (pin "B9") (pinfunction "VDD_B9") (pintype "power_in"))
      (node (ref "IC13") (pin "C1") (pinfunction "VDDQ_C1") (pintype "power_in"))
      (node (ref "IC13") (pin "D1") (pinfunction "VDD_D1") (pintype "power_in"))
      (node (ref "IC13") (pin "D9") (pinfunction "VDDQ_D9") (pintype "power_in"))
      (node (ref "IC13") (pin "F2") (pinfunction "VDDQ_F2") (pintype "power_in"))
      (node (ref "IC13") (pin "F8") (pinfunction "VDDQ_F8") (pintype "power_in"))
      (node (ref "IC13") (pin "G1") (pinfunction "VDDQ_G1") (pintype "power_in"))
      (node (ref "IC13") (pin "G7") (pinfunction "VDD_G7") (pintype "power_in"))
      (node (ref "IC13") (pin "G9") (pinfunction "VDDQ_G9") (pintype "power_in"))
      (node (ref "IC13") (pin "J1") (pinfunction "VDD_J1") (pintype "power_in"))
      (node (ref "IC13") (pin "J2") (pinfunction "VDDQ_J2") (pintype "power_in"))
      (node (ref "IC13") (pin "J8") (pinfunction "VDDQ_J8") (pintype "power_in"))
      (node (ref "IC13") (pin "J9") (pinfunction "VDD_J9") (pintype "power_in"))
      (node (ref "IC13") (pin "L1") (pinfunction "VDD_L1") (pintype "power_in"))
      (node (ref "IC13") (pin "L9") (pinfunction "VDD_L9") (pintype "power_in"))
      (node (ref "IC13") (pin "R1") (pinfunction "VDD_R1") (pintype "power_in"))
      (node (ref "IC13") (pin "T9") (pinfunction "VDD_T9") (pintype "power_in"))
      (node (ref "IC14") (pin "A1") (pinfunction "VDDQ_A1") (pintype "power_in"))
      (node (ref "IC14") (pin "A9") (pinfunction "VDDQ_A9") (pintype "power_in"))
      (node (ref "IC14") (pin "B3") (pinfunction "VDD_B3") (pintype "power_in"))
      (node (ref "IC14") (pin "B9") (pinfunction "VDD_B9") (pintype "power_in"))
      (node (ref "IC14") (pin "C1") (pinfunction "VDDQ_C1") (pintype "power_in"))
      (node (ref "IC14") (pin "D1") (pinfunction "VDD_D1") (pintype "power_in"))
      (node (ref "IC14") (pin "D9") (pinfunction "VDDQ_D9") (pintype "power_in"))
      (node (ref "IC14") (pin "F2") (pinfunction "VDDQ_F2") (pintype "power_in"))
      (node (ref "IC14") (pin "F8") (pinfunction "VDDQ_F8") (pintype "power_in"))
      (node (ref "IC14") (pin "G1") (pinfunction "VDDQ_G1") (pintype "power_in"))
      (node (ref "IC14") (pin "G7") (pinfunction "VDD_G7") (pintype "power_in"))
      (node (ref "IC14") (pin "G9") (pinfunction "VDDQ_G9") (pintype "power_in"))
      (node (ref "IC14") (pin "J1") (pinfunction "VDD_J1") (pintype "power_in"))
      (node (ref "IC14") (pin "J2") (pinfunction "VDDQ_J2") (pintype "power_in"))
      (node (ref "IC14") (pin "J8") (pinfunction "VDDQ_J8") (pintype "power_in"))
      (node (ref "IC14") (pin "J9") (pinfunction "VDD_J9") (pintype "power_in"))
      (node (ref "IC14") (pin "L1") (pinfunction "VDD_L1") (pintype "power_in"))
      (node (ref "IC14") (pin "L9") (pinfunction "VDD_L9") (pintype "power_in"))
      (node (ref "IC14") (pin "R1") (pinfunction "VDD_R1") (pintype "power_in"))
      (node (ref "IC14") (pin "T9") (pinfunction "VDD_T9") (pintype "power_in"))
      (node (ref "IC15") (pin "2") (pinfunction "VLDOIN_2") (pintype "input"))
      (node (ref "R54") (pin "1") (pinfunction "1_1") (pintype "passive"))
      (node (ref "R58") (pin "2") (pinfunction "2_2") (pintype "passive"))
      (node (ref "R61") (pin "2") (pinfunction "2_2") (pintype "passive"))
      (node (ref "R62") (pin "1") (pinfunction "1_1") (pintype "passive"))
    )
    (net (code "209") (name "P2V5") (class "Default")
      (node (ref "C27") (pin "1") (pinfunction "1_1") (pintype "passive"))
      (node (ref "C28") (pin "1") (pinfunction "1_1") (pintype "passive"))
      (node (ref "C31") (pin "1") (pinfunction "1_1") (pintype "passive"))
      (node (ref "C32") (pin "1") (pinfunction "1_1") (pintype "passive"))
      (node (ref "IC13") (pin "B1") (pinfunction "VPP_B1") (pintype "power_in"))
      (node (ref "IC13") (pin "R9") (pinfunction "VPP_R9") (pintype "power_in"))
      (node (ref "IC14") (pin "B1") (pinfunction "VPP_B1") (pintype "power_in"))
      (node (ref "IC14") (pin "R9") (pinfunction "VPP_R9") (pintype "power_in"))
    )
    (net (code "210") (name "P3V3") (class "Default")
      (node (ref "C29") (pin "1") (pinfunction "1_1") (pintype "passive"))
      (node (ref "IC15") (pin "10") (pinfunction "VIN_10") (pintype "input"))
      (node (ref "IC15") (pin "7") (pinfunction "EN_7") (pintype "input"))
      (node (ref "R60") (pin "2") (pinfunction "2_2") (pintype "passive"))
    )
    (net (code "211") (name "VTT32") (class "Default")
      (node (ref "C33") (pin "2") (pinfunction "2_2") (pintype "passive"))
      (node (ref "C35") (pin "2") (pinfunction "2_2") (pintype "passive"))
      (node (ref "C51") (pin "1") (pinfunction "1_1") (pintype "passive"))
      (node (ref "C52") (pin "1") (pinfunction "1_1") (pintype "passive"))
      (node (ref "C53") (pin "1") (pinfunction "1_1") (pintype "passive"))
      (node (ref "C54") (pin "1") (pinfunction "1_1") (pintype "passive"))
      (node (ref "C58") (pin "1") (pinfunction "1_1") (pintype "passive"))
      (node (ref "C70") (pin "1") (pinfunction "1_1") (pintype "passive"))
      (node (ref "C71") (pin "1") (pinfunction "1_1") (pintype "passive"))
      (node (ref "C72") (pin "1") (pinfunction "1_1") (pintype "passive"))
      (node (ref "C73") (pin "1") (pinfunction "1_1") (pintype "passive"))
      (node (ref "C86") (pin "1") (pinfunction "1_1") (pintype "passive"))
      (node (ref "C87") (pin "1") (pinfunction "1_1") (pintype "passive"))
      (node (ref "C88") (pin "1") (pinfunction "1_1") (pintype "passive"))
      (node (ref "C89") (pin "1") (pinfunction "1_1") (pintype "passive"))
      (node (ref "IC15") (pin "3") (pinfunction "VO_3") (pintype "power_in"))
      (node (ref "R169") (pin "1") (pinfunction "1_1") (pintype "passive"))
      (node (ref "R170") (pin "1") (pinfunction "1_1") (pintype "passive"))
      (node (ref "R28") (pin "1") (pinfunction "1_1") (pintype "passive"))
      (node (ref "R29") (pin "1") (pinfunction "1_1") (pintype "passive"))
      (node (ref "R30") (pin "1") (pinfunction "1_1") (pintype "passive"))
      (node (ref "R31") (pin "1") (pinfunction "1_1") (pintype "passive"))
      (node (ref "R32") (pin "1") (pinfunction "1_1") (pintype "passive"))
      (node (ref "R33") (pin "1") (pinfunction "1_1") (pintype "passive"))
      (node (ref "R34") (pin "1") (pinfunction "1_1") (pintype "passive"))
      (node (ref "R35") (pin "1") (pinfunction "1_1") (pintype "passive"))
      (node (ref "R36") (pin "1") (pinfunction "1_1") (pintype "passive"))
      (node (ref "R37") (pin "1") (pinfunction "1_1") (pintype "passive"))
      (node (ref "R38") (pin "1") (pinfunction "1_1") (pintype "passive"))
      (node (ref "R39") (pin "1") (pinfunction "1_1") (pintype "passive"))
      (node (ref "R40") (pin "1") (pinfunction "1_1") (pintype "passive"))
      (node (ref "R41") (pin "1") (pinfunction "1_1") (pintype "passive"))
      (node (ref "R42") (pin "1") (pinfunction "1_1") (pintype "passive"))
      (node (ref "R45") (pin "1") (pinfunction "1_1") (pintype "passive"))
      (node (ref "R47") (pin "1") (pinfunction "1_1") (pintype "passive"))
      (node (ref "R48") (pin "1") (pinfunction "1_1") (pintype "passive"))
      (node (ref "R49") (pin "1") (pinfunction "1_1") (pintype "passive"))
      (node (ref "R51") (pin "1") (pinfunction "1_1") (pintype "passive"))
      (node (ref "R52") (pin "1") (pinfunction "1_1") (pintype "passive"))
      (node (ref "R53") (pin "1") (pinfunction "1_1") (pintype "passive"))
      (node (ref "R55") (pin "1") (pinfunction "1_1") (pintype "passive"))
      (node (ref "R63") (pin "2") (pinfunction "2_2") (pintype "passive"))
    )
    (net (code "212") (name "unconnected-(IC13-NC-PadT7)") (class "Default")
      (node (ref "IC13") (pin "T7") (pinfunction "NC_T7") (pintype "power_in"))
    )
    (net (code "213") (name "unconnected-(IC14-NC-PadT7)") (class "Default")
      (node (ref "IC14") (pin "T7") (pinfunction "NC_T7") (pintype "power_in"))
    )
  )
)
